# homeboard3.net
KiCad netlist of a schematic drawn in EAGLE
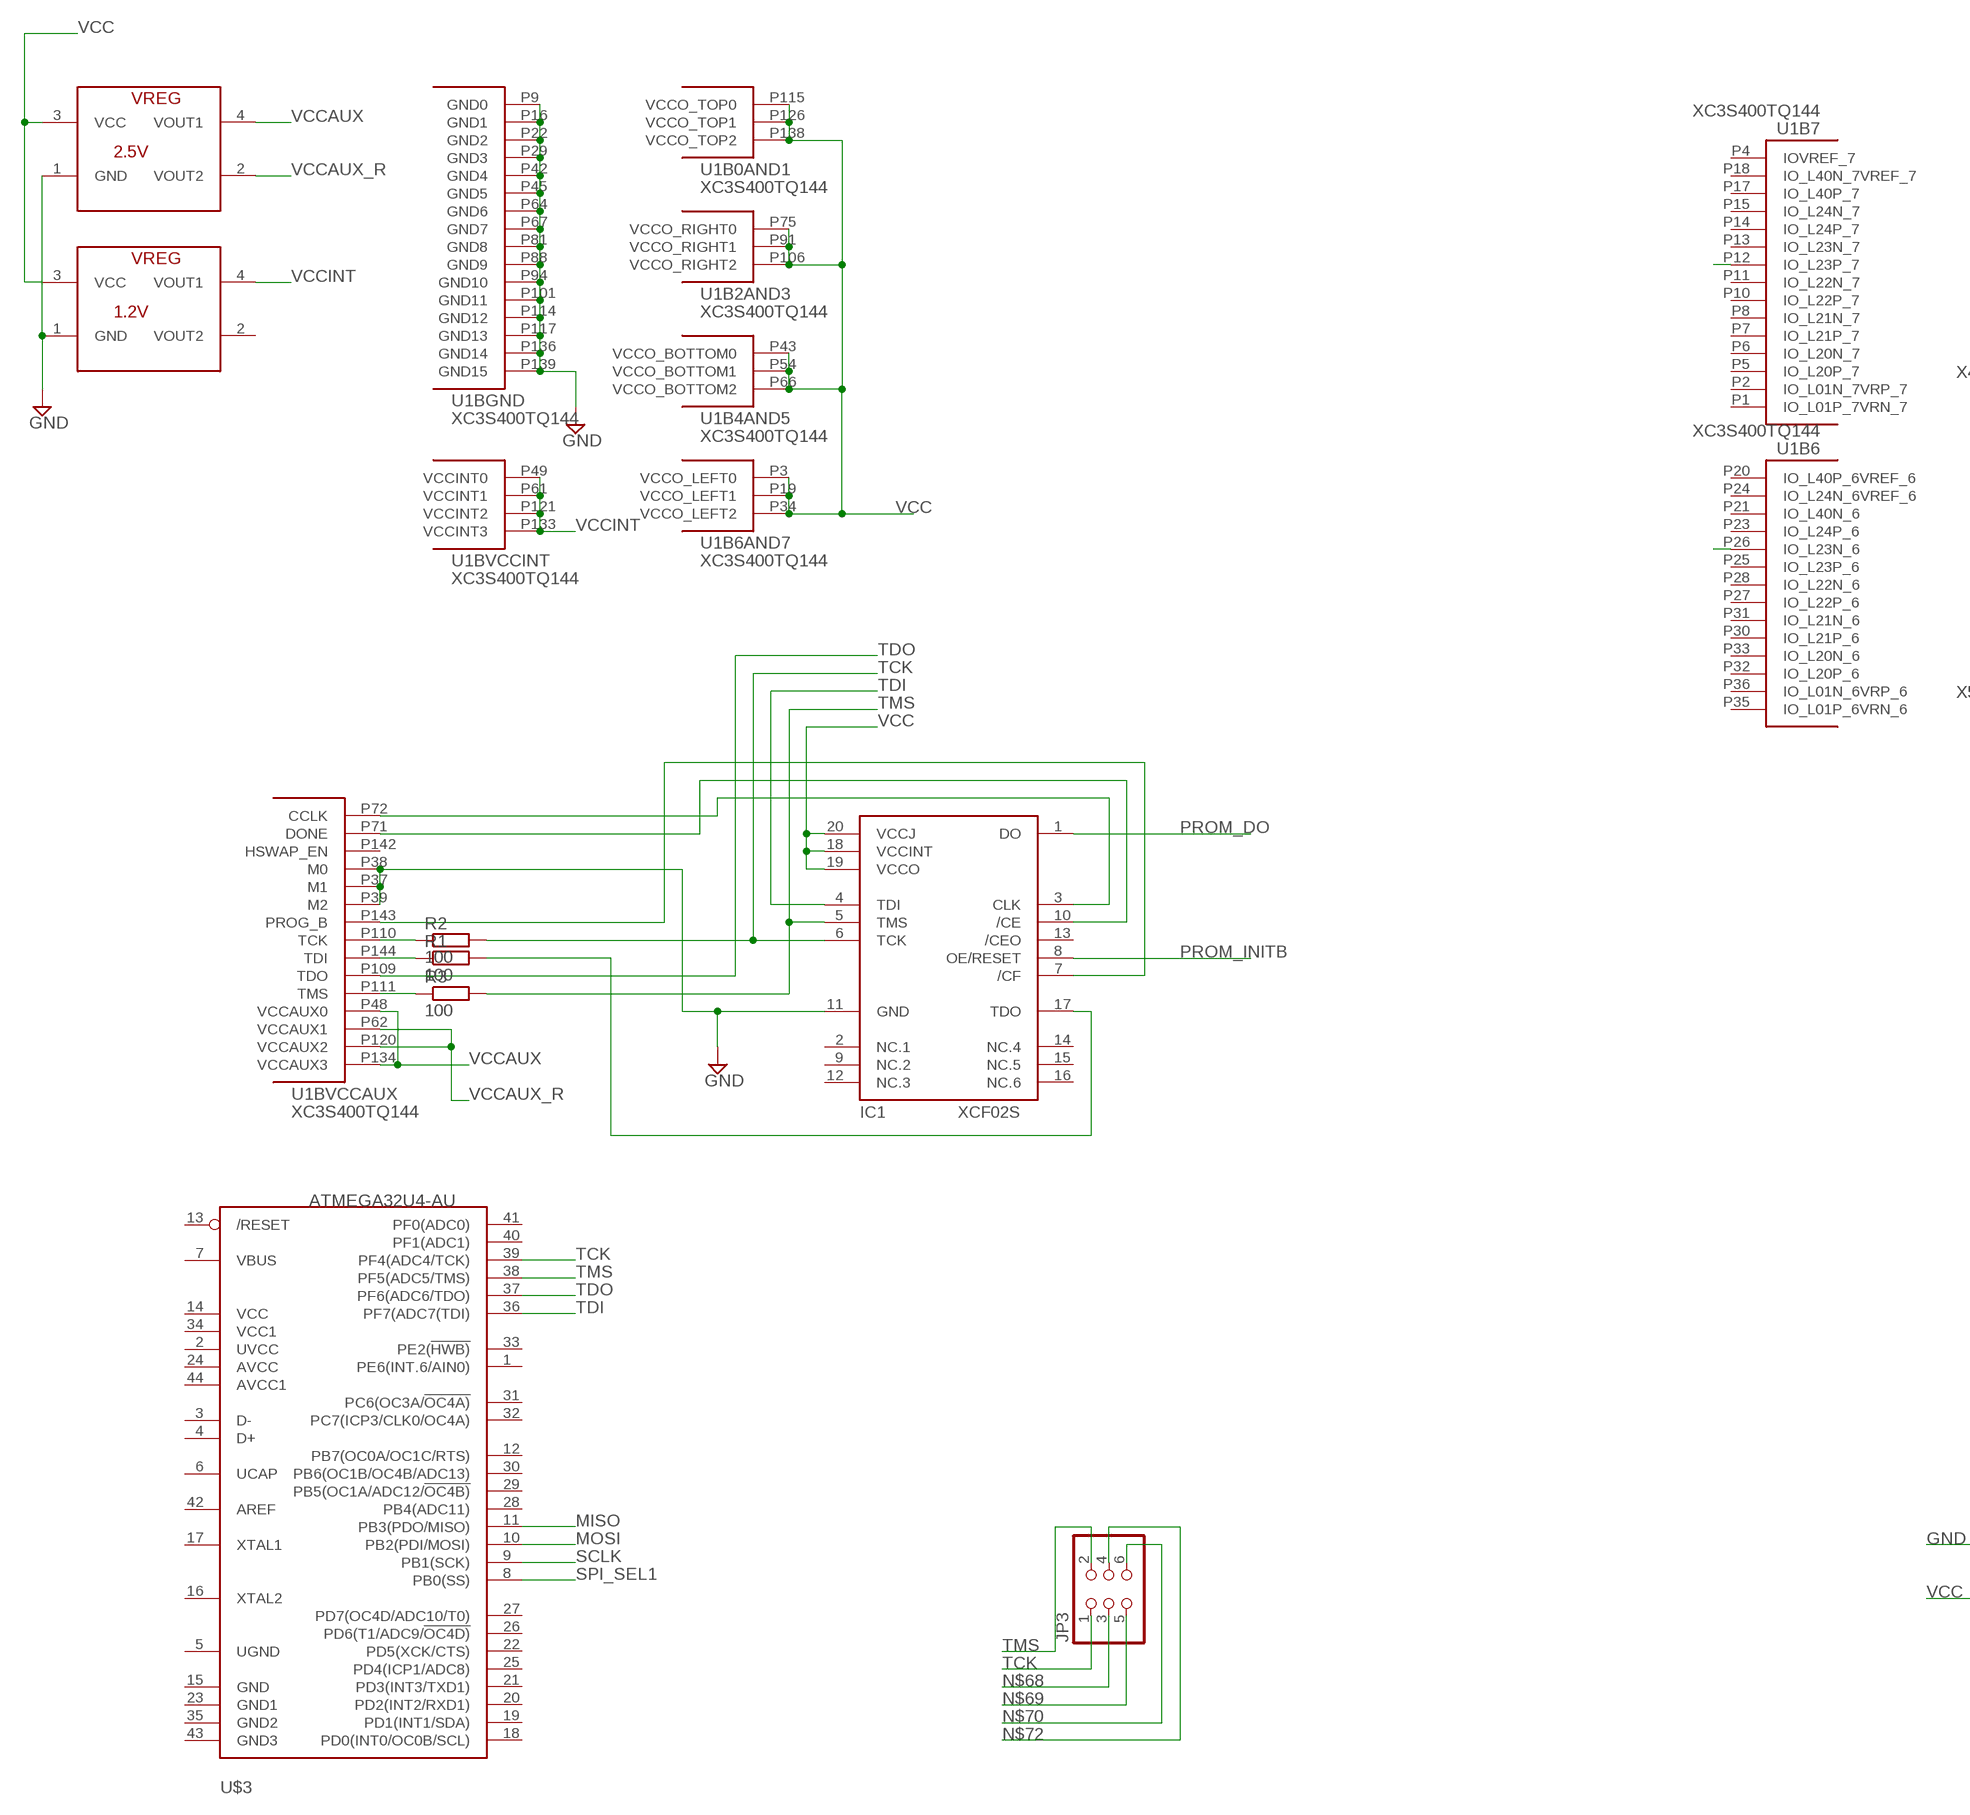
[diagram p0: schematic, sheet 1, part 1 of 3]
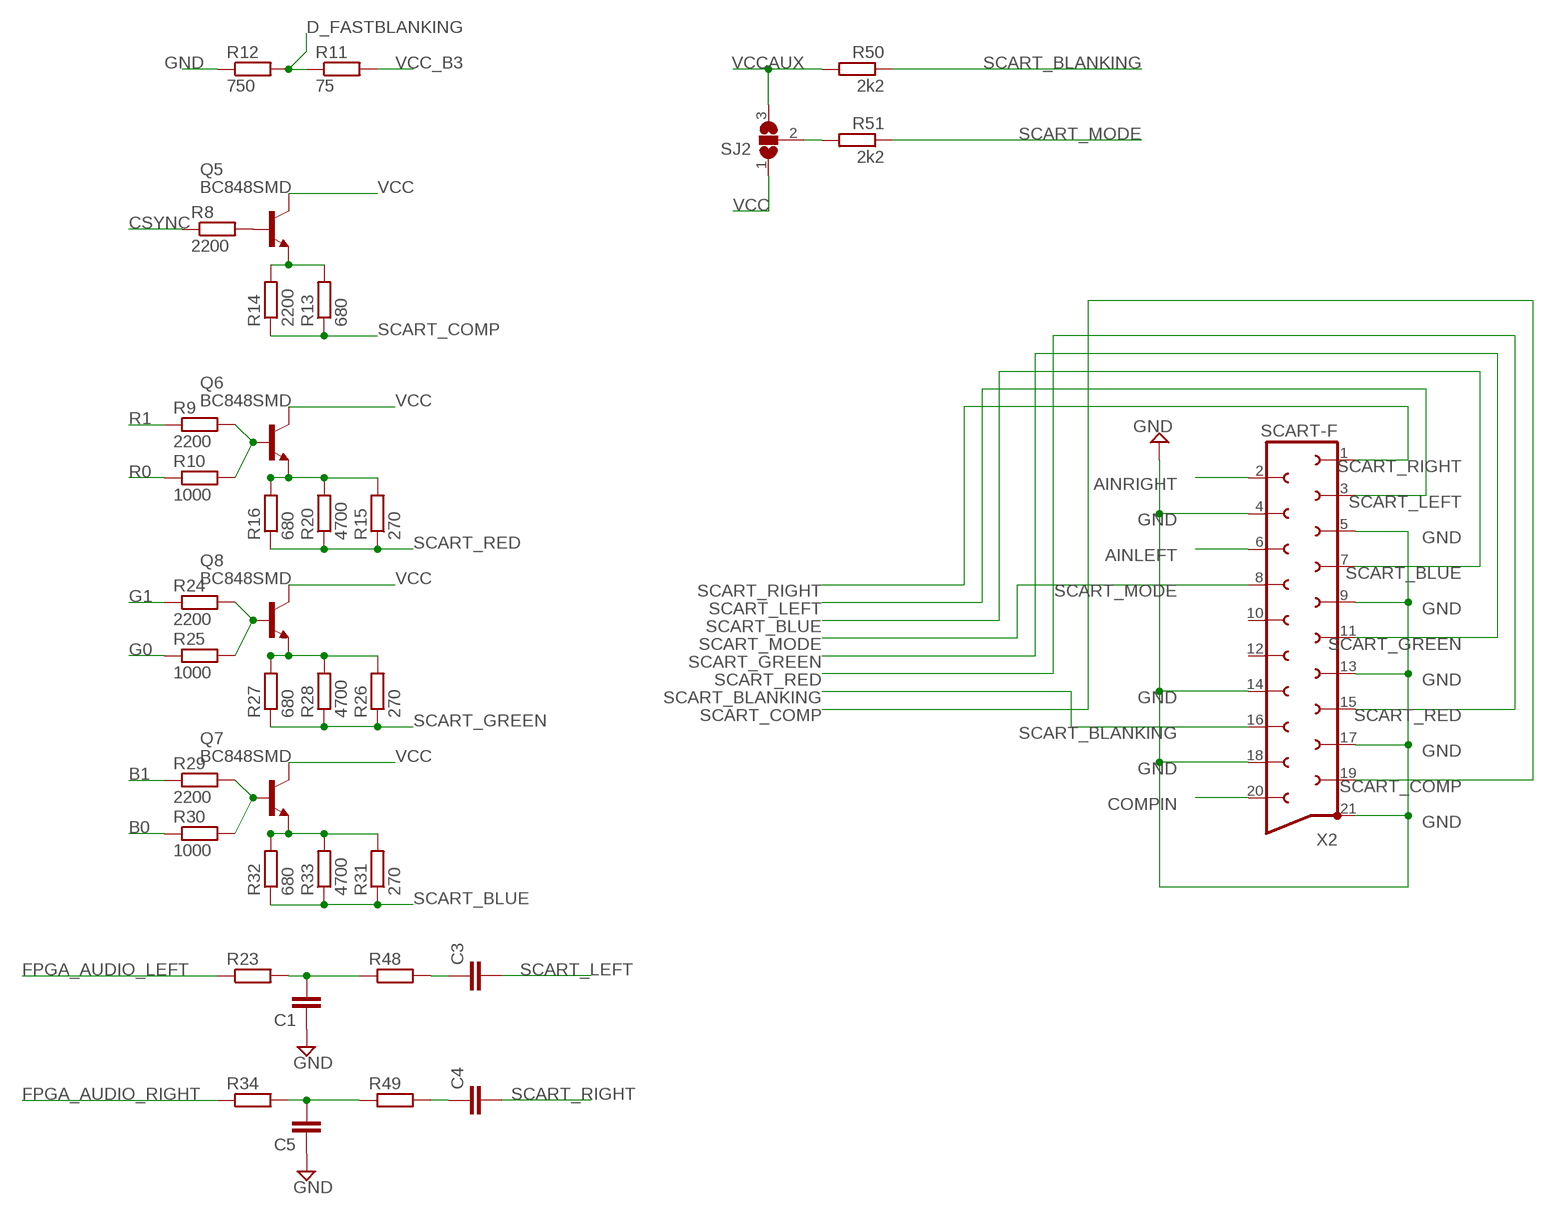
[diagram p1: schematic, sheet 1, part 2 of 3]
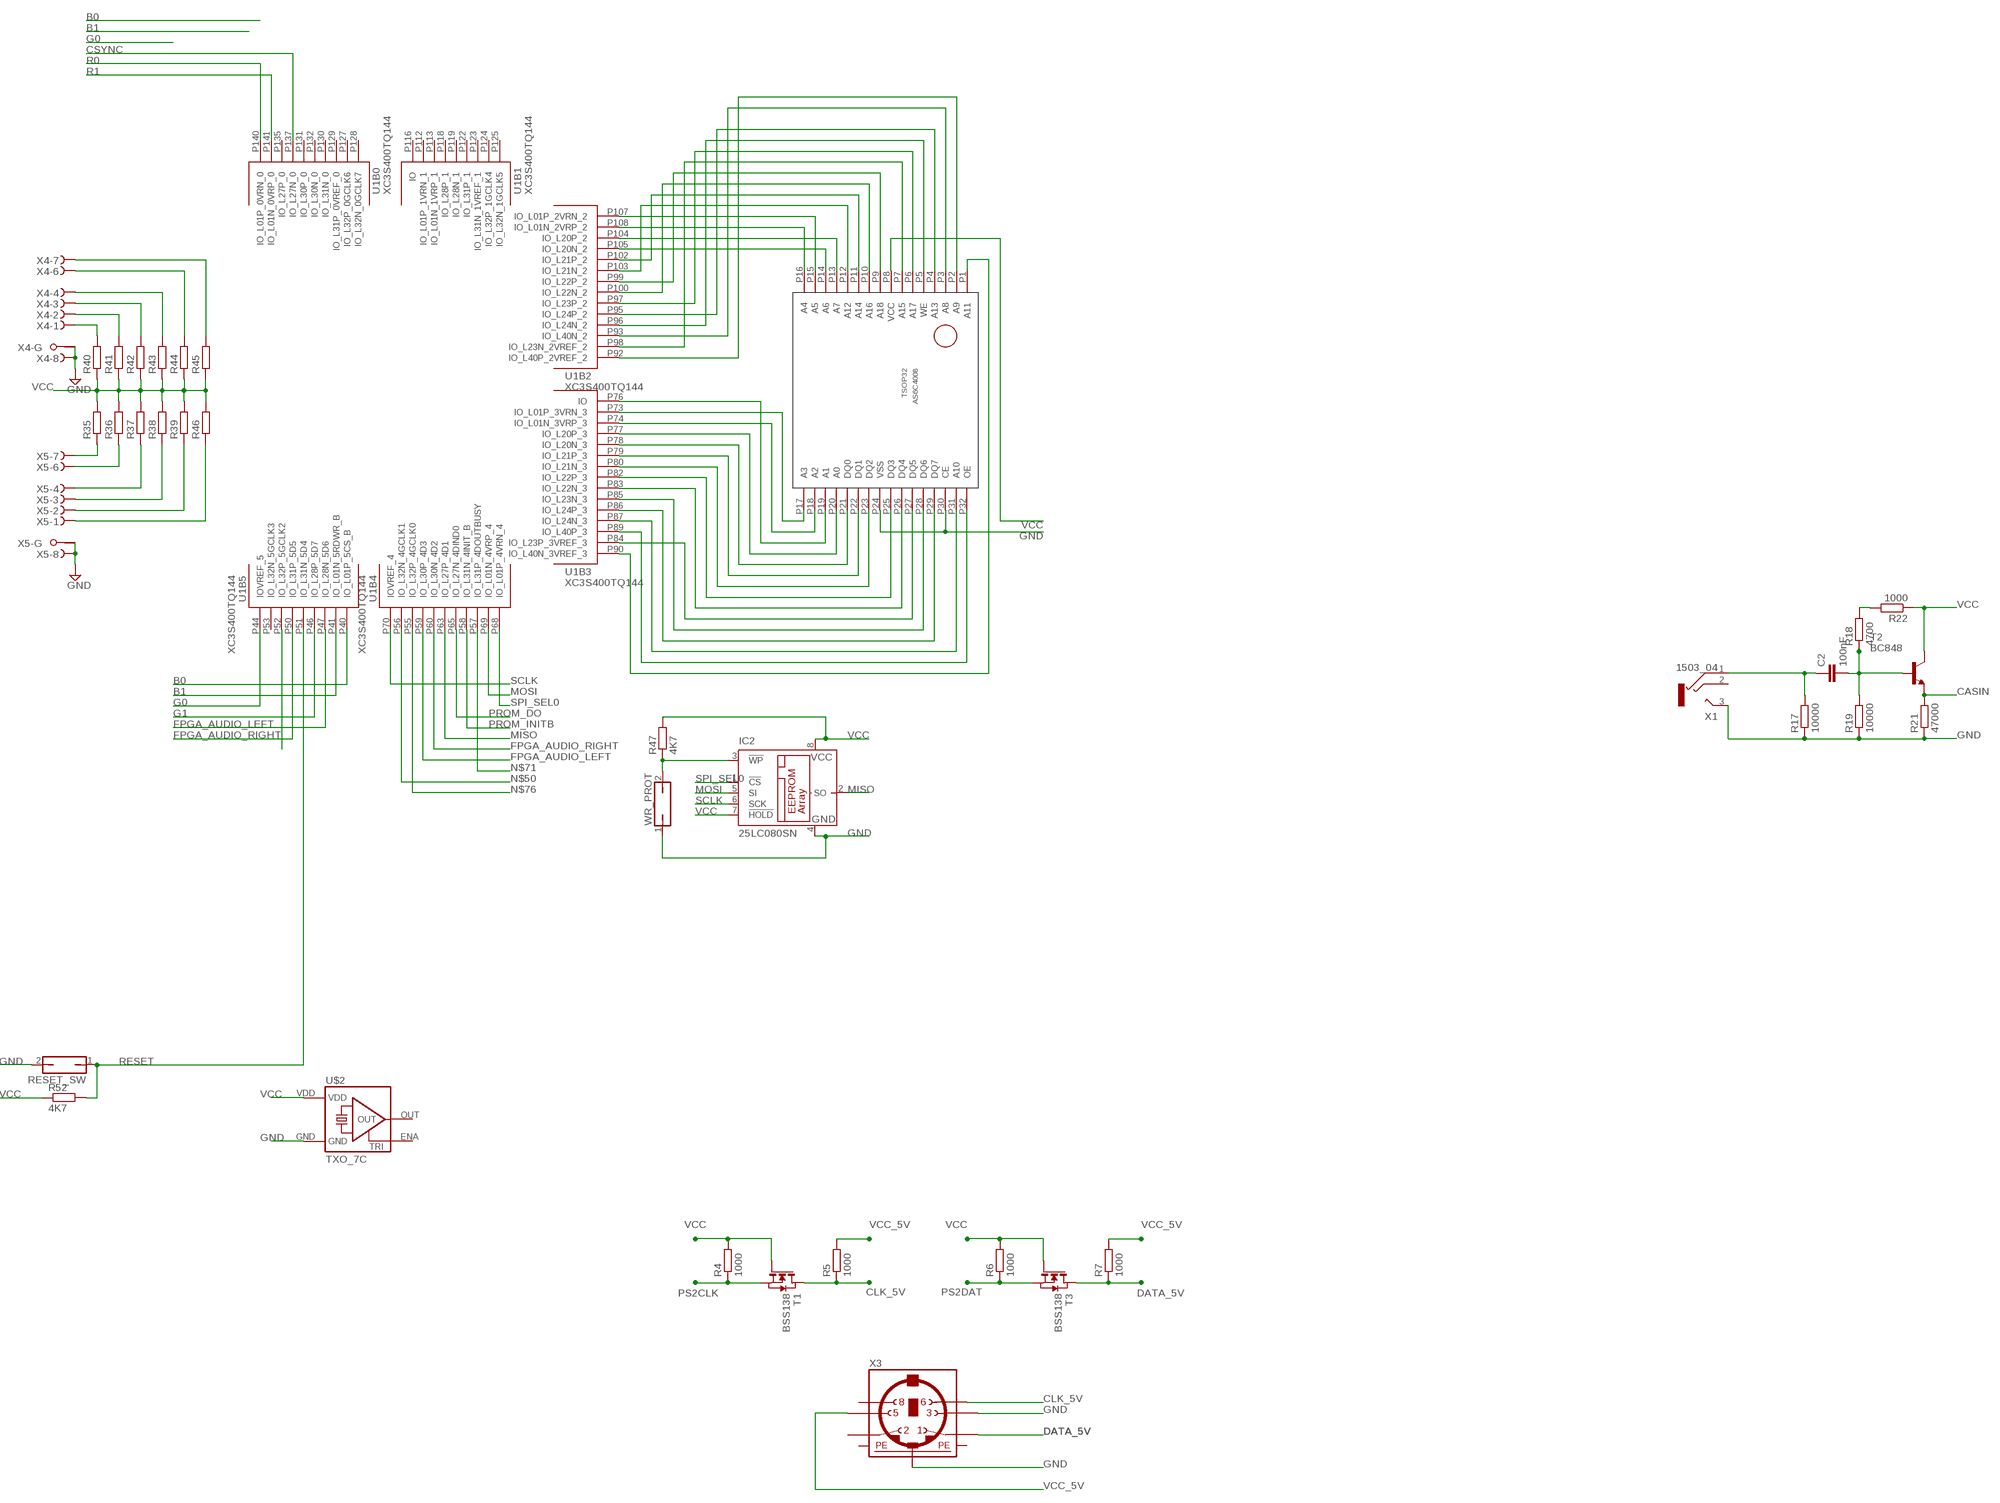
[diagram p2: schematic, sheet 1, part 3 of 3]

(export (version "E")
  (design (tool "Eeschema 10.0.6"))
  (components
    (comp (ref "C1")
      (value "C-EUC0603")
      (footprint "eagle-import:C0603")
      (libsource (lib "eagle-import") (part "C-EUC0603"))
    )
    (comp (ref "C2")
      (value "100nF")
      (footprint "eagle-import:C0603")
      (libsource (lib "eagle-import") (part "C-EUC0603"))
    )
    (comp (ref "C3")
      (value "C-EUC0603")
      (footprint "eagle-import:C0603")
      (libsource (lib "eagle-import") (part "C-EUC0603"))
    )
    (comp (ref "C4")
      (value "C-EUC0603")
      (footprint "eagle-import:C0603")
      (libsource (lib "eagle-import") (part "C-EUC0603"))
    )
    (comp (ref "C5")
      (value "C-EUC0603")
      (footprint "eagle-import:C0603")
      (libsource (lib "eagle-import") (part "C-EUC0603"))
    )
    (comp (ref "IC1")
      (value "XCF02S")
      (footprint "eagle-import:VO20")
      (libsource (lib "eagle-import") (part "XCF02S"))
    )
    (comp (ref "IC2")
      (value "25LC080SN")
      (footprint "eagle-import:SO-08")
      (fields (field (name "MF") "MICROCHIP") (field (name "MPN") "25LC080/SN"))
      (libsource (lib "eagle-import") (part "25SNLC080"))
    )
    (comp (ref "JP3")
      (value "PINHD-2X3")
      (footprint "eagle-import:2X03")
      (libsource (lib "eagle-import") (part "PINHD-2X3"))
    )
    (comp (ref "Q5")
      (value "BC848SMD")
      (footprint "eagle-import:SOT23")
      (libsource (lib "eagle-import") (part "BC848SMD"))
    )
    (comp (ref "Q6")
      (value "BC848SMD")
      (footprint "eagle-import:SOT23")
      (libsource (lib "eagle-import") (part "BC848SMD"))
    )
    (comp (ref "Q7")
      (value "BC848SMD")
      (footprint "eagle-import:SOT23")
      (libsource (lib "eagle-import") (part "BC848SMD"))
    )
    (comp (ref "Q8")
      (value "BC848SMD")
      (footprint "eagle-import:SOT23")
      (libsource (lib "eagle-import") (part "BC848SMD"))
    )
    (comp (ref "R1")
      (value "100")
      (footprint "eagle-import:R0805")
      (libsource (lib "eagle-import") (part "R-EU_R0805"))
    )
    (comp (ref "R2")
      (value "100")
      (footprint "eagle-import:R0805")
      (libsource (lib "eagle-import") (part "R-EU_R0805"))
    )
    (comp (ref "R3")
      (value "100")
      (footprint "eagle-import:R0805")
      (libsource (lib "eagle-import") (part "R-EU_R0805"))
    )
    (comp (ref "R4")
      (value "1000")
      (footprint "eagle-import:R0805")
      (libsource (lib "eagle-import") (part "R-EU_R0805"))
    )
    (comp (ref "R5")
      (value "1000")
      (footprint "eagle-import:R0805")
      (libsource (lib "eagle-import") (part "R-EU_R0805"))
    )
    (comp (ref "R6")
      (value "1000")
      (footprint "eagle-import:R0805")
      (libsource (lib "eagle-import") (part "R-EU_R0805"))
    )
    (comp (ref "R7")
      (value "1000")
      (footprint "eagle-import:R0805")
      (libsource (lib "eagle-import") (part "R-EU_R0805"))
    )
    (comp (ref "R8")
      (value "2200")
      (footprint "eagle-import:R0805")
      (libsource (lib "eagle-import") (part "R-EU_R0805"))
    )
    (comp (ref "R9")
      (value "2200")
      (footprint "eagle-import:R0805")
      (libsource (lib "eagle-import") (part "R-EU_R0805"))
    )
    (comp (ref "R10")
      (value "1000")
      (footprint "eagle-import:R0805")
      (libsource (lib "eagle-import") (part "R-EU_R0805"))
    )
    (comp (ref "R11")
      (value "75")
      (footprint "eagle-import:R0805")
      (libsource (lib "eagle-import") (part "R-EU_R0805"))
    )
    (comp (ref "R12")
      (value "750")
      (footprint "eagle-import:R0805")
      (libsource (lib "eagle-import") (part "R-EU_R0805"))
    )
    (comp (ref "R13")
      (value "680")
      (footprint "eagle-import:R0805")
      (libsource (lib "eagle-import") (part "R-EU_R0805"))
    )
    (comp (ref "R14")
      (value "2200")
      (footprint "eagle-import:R0805")
      (libsource (lib "eagle-import") (part "R-EU_R0805"))
    )
    (comp (ref "R15")
      (value "270")
      (footprint "eagle-import:R0805")
      (libsource (lib "eagle-import") (part "R-EU_R0805"))
    )
    (comp (ref "R16")
      (value "680")
      (footprint "eagle-import:R0805")
      (libsource (lib "eagle-import") (part "R-EU_R0805"))
    )
    (comp (ref "R17")
      (value "10000")
      (footprint "eagle-import:R0805")
      (libsource (lib "eagle-import") (part "R-EU_R0805"))
    )
    (comp (ref "R18")
      (value "4700")
      (footprint "eagle-import:R0805")
      (libsource (lib "eagle-import") (part "R-EU_R0805"))
    )
    (comp (ref "R19")
      (value "10000")
      (footprint "eagle-import:R0805")
      (libsource (lib "eagle-import") (part "R-EU_R0805"))
    )
    (comp (ref "R20")
      (value "4700")
      (footprint "eagle-import:R0805")
      (libsource (lib "eagle-import") (part "R-EU_R0805"))
    )
    (comp (ref "R21")
      (value "47000")
      (footprint "eagle-import:R0805")
      (libsource (lib "eagle-import") (part "R-EU_R0805"))
    )
    (comp (ref "R22")
      (value "1000")
      (footprint "eagle-import:R0805")
      (libsource (lib "eagle-import") (part "R-EU_R0805"))
    )
    (comp (ref "R23")
      (value "R-EU_M0805")
      (footprint "eagle-import:M0805")
      (libsource (lib "eagle-import") (part "resistor_R-EU_M0805"))
    )
    (comp (ref "R24")
      (value "2200")
      (footprint "eagle-import:R0805")
      (libsource (lib "eagle-import") (part "R-EU_R0805"))
    )
    (comp (ref "R25")
      (value "1000")
      (footprint "eagle-import:R0805")
      (libsource (lib "eagle-import") (part "R-EU_R0805"))
    )
    (comp (ref "R26")
      (value "270")
      (footprint "eagle-import:R0805")
      (libsource (lib "eagle-import") (part "R-EU_R0805"))
    )
    (comp (ref "R27")
      (value "680")
      (footprint "eagle-import:R0805")
      (libsource (lib "eagle-import") (part "R-EU_R0805"))
    )
    (comp (ref "R28")
      (value "4700")
      (footprint "eagle-import:R0805")
      (libsource (lib "eagle-import") (part "R-EU_R0805"))
    )
    (comp (ref "R29")
      (value "2200")
      (footprint "eagle-import:R0805")
      (libsource (lib "eagle-import") (part "R-EU_R0805"))
    )
    (comp (ref "R30")
      (value "1000")
      (footprint "eagle-import:R0805")
      (libsource (lib "eagle-import") (part "R-EU_R0805"))
    )
    (comp (ref "R31")
      (value "270")
      (footprint "eagle-import:R0805")
      (libsource (lib "eagle-import") (part "R-EU_R0805"))
    )
    (comp (ref "R32")
      (value "680")
      (footprint "eagle-import:R0805")
      (libsource (lib "eagle-import") (part "R-EU_R0805"))
    )
    (comp (ref "R33")
      (value "4700")
      (footprint "eagle-import:R0805")
      (libsource (lib "eagle-import") (part "R-EU_R0805"))
    )
    (comp (ref "R34")
      (value "R-EU_M0805")
      (footprint "eagle-import:M0805")
      (libsource (lib "eagle-import") (part "resistor_R-EU_M0805"))
    )
    (comp (ref "R35")
      (value "R-EU_M0805")
      (footprint "eagle-import:M0805")
      (libsource (lib "eagle-import") (part "resistor_R-EU_M0805"))
    )
    (comp (ref "R36")
      (value "R-EU_M0805")
      (footprint "eagle-import:M0805")
      (libsource (lib "eagle-import") (part "resistor_R-EU_M0805"))
    )
    (comp (ref "R37")
      (value "R-EU_M0805")
      (footprint "eagle-import:M0805")
      (libsource (lib "eagle-import") (part "resistor_R-EU_M0805"))
    )
    (comp (ref "R38")
      (value "R-EU_M0805")
      (footprint "eagle-import:M0805")
      (libsource (lib "eagle-import") (part "resistor_R-EU_M0805"))
    )
    (comp (ref "R39")
      (value "R-EU_M0805")
      (footprint "eagle-import:M0805")
      (libsource (lib "eagle-import") (part "resistor_R-EU_M0805"))
    )
    (comp (ref "R40")
      (value "R-EU_M0805")
      (footprint "eagle-import:M0805")
      (libsource (lib "eagle-import") (part "resistor_R-EU_M0805"))
    )
    (comp (ref "R41")
      (value "R-EU_M0805")
      (footprint "eagle-import:M0805")
      (libsource (lib "eagle-import") (part "resistor_R-EU_M0805"))
    )
    (comp (ref "R42")
      (value "R-EU_M0805")
      (footprint "eagle-import:M0805")
      (libsource (lib "eagle-import") (part "resistor_R-EU_M0805"))
    )
    (comp (ref "R43")
      (value "R-EU_M0805")
      (footprint "eagle-import:M0805")
      (libsource (lib "eagle-import") (part "resistor_R-EU_M0805"))
    )
    (comp (ref "R44")
      (value "R-EU_M0805")
      (footprint "eagle-import:M0805")
      (libsource (lib "eagle-import") (part "resistor_R-EU_M0805"))
    )
    (comp (ref "R45")
      (value "R-EU_M0805")
      (footprint "eagle-import:M0805")
      (libsource (lib "eagle-import") (part "resistor_R-EU_M0805"))
    )
    (comp (ref "R46")
      (value "R-EU_M0805")
      (footprint "eagle-import:M0805")
      (libsource (lib "eagle-import") (part "resistor_R-EU_M0805"))
    )
    (comp (ref "R47")
      (value "4K7")
      (footprint "eagle-import:R0805")
      (libsource (lib "eagle-import") (part "R-EU_R0805"))
    )
    (comp (ref "R48")
      (value "R-EU_M0805")
      (footprint "eagle-import:M0805")
      (libsource (lib "eagle-import") (part "resistor_R-EU_M0805"))
    )
    (comp (ref "R49")
      (value "R-EU_M0805")
      (footprint "eagle-import:M0805")
      (libsource (lib "eagle-import") (part "resistor_R-EU_M0805"))
    )
    (comp (ref "R50")
      (value "2k2")
      (footprint "eagle-import:M0805")
      (libsource (lib "eagle-import") (part "resistor_R-EU_M0805"))
    )
    (comp (ref "R51")
      (value "2k2")
      (footprint "eagle-import:M0805")
      (libsource (lib "eagle-import") (part "resistor_R-EU_M0805"))
    )
    (comp (ref "R52")
      (value "4K7")
      (footprint "eagle-import:M0805")
      (libsource (lib "eagle-import") (part "resistor_R-EU_M0805"))
    )
    (comp (ref "REG1.2")
      (value "1.2V")
      (footprint "eagle-import:SOT223")
      (libsource (lib "eagle-import") (part "NX1117"))
    )
    (comp (ref "REG2.5")
      (value "2.5V")
      (footprint "eagle-import:SOT223")
      (libsource (lib "eagle-import") (part "NX1117"))
    )
    (comp (ref "RESET_SW")
      (value "JP1Q")
      (footprint "eagle-import:JP1")
      (libsource (lib "eagle-import") (part "JP1Q"))
    )
    (comp (ref "SJ2")
      (value "SJ2W")
      (footprint "eagle-import:SJ_2")
      (libsource (lib "eagle-import") (part "SJ2W"))
    )
    (comp (ref "T1")
      (value "BSS138")
      (footprint "eagle-import:SOT-23")
      (libsource (lib "eagle-import") (part "NMOSSOT23"))
    )
    (comp (ref "T2")
      (value "BC848")
      (footprint "eagle-import:SOT23")
      (libsource (lib "eagle-import") (part "BC848"))
    )
    (comp (ref "T3")
      (value "BSS138")
      (footprint "eagle-import:SOT-23")
      (libsource (lib "eagle-import") (part "NMOSSOT23"))
    )
    (comp (ref "U$1")
      (value "AS6C4008")
      (footprint "eagle-import:TSOP32")
      (libsource (lib "eagle-import") (part "AS6C4008"))
    )
    (comp (ref "U$2")
      (value "TXO_7C")
      (footprint "eagle-import:OSC_7C")
      (libsource (lib "eagle-import") (part "TXO_7C"))
    )
    (comp (ref "U$3")
      (value "ATMEGA32U4-AU")
      (footprint "eagle-import:TQFP44")
      (libsource (lib "eagle-import") (part "ATMEGA32U4-AU"))
    )
    (comp (ref "U1")
      (value "XC3S400TQ144")
      (footprint "eagle-import:TQ144")
      (libsource (lib "eagle-import") (part "XC3S400TQ144"))
    )
    (comp (ref "WR_PROT")
      (value "JP1Q")
      (footprint "eagle-import:JP1")
      (libsource (lib "eagle-import") (part "JP1Q"))
    )
    (comp (ref "X1")
      (value "1503_04")
      (footprint "eagle-import:1503_04")
      (libsource (lib "eagle-import") (part "1503_04"))
    )
    (comp (ref "X2")
      (value "SCART-F")
      (footprint "eagle-import:SCART-F")
      (libsource (lib "eagle-import") (part "SCART-F"))
    )
    (comp (ref "X3")
      (value "MINI_DIN_6")
      (footprint "eagle-import:M_DIN6")
      (libsource (lib "eagle-import") (part "MINI_DIN_6"))
    )
    (comp (ref "X4")
      (value "F09HPS")
      (footprint "eagle-import:F09HP")
      (libsource (lib "eagle-import") (part "F09HPS"))
    )
    (comp (ref "X5")
      (value "F09HPS")
      (footprint "eagle-import:F09HP")
      (libsource (lib "eagle-import") (part "F09HPS"))
    )
  )
  (nets
    (net (code "1") (name "/AINLEFT") (class "Default")
      (node (ref "X2") (pin "6") (pinfunction "6_6") (pintype "passive"))
    )
    (net (code "2") (name "/AINRIGHT") (class "Default")
      (node (ref "X2") (pin "2") (pinfunction "2_2") (pintype "passive"))
    )
    (net (code "3") (name "/B0") (class "Default")
      (node (ref "R30") (pin "1") (pinfunction "1_1") (pintype "passive"))
      (node (ref "U1") (pin "P40") (pinfunction "IO_L01P_5CS_B_P40") (pintype "bidirectional"))
    )
    (net (code "4") (name "/B1") (class "Default")
      (node (ref "R29") (pin "1") (pinfunction "1_1") (pintype "passive"))
      (node (ref "U1") (pin "P41") (pinfunction "IO_L01N_5RDWR_B_P41") (pintype "bidirectional"))
    )
    (net (code "5") (name "/CASIN") (class "Default")
      (node (ref "R21") (pin "2") (pinfunction "2_2") (pintype "passive"))
      (node (ref "T2") (pin "2") (pinfunction "E_2") (pintype "passive"))
    )
    (net (code "6") (name "/CLK_5V") (class "Default")
      (node (ref "R5") (pin "1") (pinfunction "1_1") (pintype "passive"))
      (node (ref "T1") (pin "1") (pinfunction "D_1") (pintype "passive"))
      (node (ref "X3") (pin "6") (pinfunction "6_6") (pintype "passive"))
    )
    (net (code "7") (name "/COMPIN") (class "Default")
      (node (ref "X2") (pin "20") (pinfunction "20_20") (pintype "passive"))
    )
    (net (code "8") (name "/CSYNC") (class "Default")
      (node (ref "R8") (pin "1") (pinfunction "1_1") (pintype "passive"))
      (node (ref "U1") (pin "P137") (pinfunction "IO_L27N_0_P137") (pintype "bidirectional"))
    )
    (net (code "9") (name "/DATA_5V") (class "Default")
      (node (ref "R7") (pin "1") (pinfunction "1_1") (pintype "passive"))
      (node (ref "T3") (pin "1") (pinfunction "D_1") (pintype "passive"))
      (node (ref "X3") (pin "1") (pinfunction "1_1") (pintype "passive"))
    )
    (net (code "10") (name "/D_FASTBLANKING") (class "Default")
      (node (ref "R11") (pin "1") (pinfunction "1_1") (pintype "passive"))
      (node (ref "R12") (pin "2") (pinfunction "2_2") (pintype "passive"))
    )
    (net (code "11") (name "/FPGA_AUDIO_LEFT") (class "Default")
      (node (ref "R23") (pin "1") (pinfunction "1_1") (pintype "passive"))
      (node (ref "U1") (pin "P47") (pinfunction "IO_L28N_5D6_P47") (pintype "bidirectional"))
      (node (ref "U1") (pin "P59") (pinfunction "IO_L30P_4D3_P59") (pintype "bidirectional"))
    )
    (net (code "12") (name "/FPGA_AUDIO_RIGHT") (class "Default")
      (node (ref "R34") (pin "1") (pinfunction "1_1") (pintype "passive"))
      (node (ref "U1") (pin "P50") (pinfunction "IO_L31P_5D5_P50") (pintype "bidirectional"))
      (node (ref "U1") (pin "P60") (pinfunction "IO_L30N_4D2_P60") (pintype "bidirectional"))
    )
    (net (code "13") (name "/G0") (class "Default")
      (node (ref "R25") (pin "1") (pinfunction "1_1") (pintype "passive"))
      (node (ref "U1") (pin "P44") (pinfunction "IOVREF_5_P44") (pintype "bidirectional"))
    )
    (net (code "14") (name "/G1") (class "Default")
      (node (ref "R24") (pin "1") (pinfunction "1_1") (pintype "passive"))
      (node (ref "U1") (pin "P46") (pinfunction "IO_L28P_5D7_P46") (pintype "bidirectional"))
    )
    (net (code "15") (name "/MISO") (class "Default")
      (node (ref "IC2") (pin "2") (pinfunction "SO_2") (pintype "bidirectional"))
      (node (ref "U$3") (pin "11") (pinfunction "PB3(PDO/MISO)_11") (pintype "bidirectional"))
      (node (ref "U1") (pin "P63") (pinfunction "IO_L27P_4D1_P63") (pintype "bidirectional"))
    )
    (net (code "16") (name "/MOSI") (class "Default")
      (node (ref "IC2") (pin "5") (pinfunction "SI_5") (pintype "input"))
      (node (ref "U$3") (pin "10") (pinfunction "PB2(PDI/MOSI)_10") (pintype "bidirectional"))
      (node (ref "U1") (pin "P69") (pinfunction "IO_L01N_4VRP_4_P69") (pintype "bidirectional"))
    )
    (net (code "17") (name "/N$50") (class "Default")
      (node (ref "U1") (pin "P56") (pinfunction "IO_L32N_4GCLK1_P56") (pintype "bidirectional"))
    )
    (net (code "18") (name "/N$68") (class "Default")
      (node (ref "JP3") (pin "3") (pinfunction "3_3") (pintype "passive"))
    )
    (net (code "19") (name "/N$69") (class "Default")
      (node (ref "JP3") (pin "5") (pinfunction "5_5") (pintype "passive"))
    )
    (net (code "20") (name "/N$70") (class "Default")
      (node (ref "JP3") (pin "6") (pinfunction "6_6") (pintype "passive"))
    )
    (net (code "21") (name "/N$71") (class "Default")
      (node (ref "U1") (pin "P57") (pinfunction "IO_L31P_4DOUTBUSY_P57") (pintype "bidirectional"))
    )
    (net (code "22") (name "/N$72") (class "Default")
      (node (ref "JP3") (pin "4") (pinfunction "4_4") (pintype "passive"))
    )
    (net (code "23") (name "/N$76") (class "Default")
      (node (ref "U1") (pin "P55") (pinfunction "IO_L32P_4GCLK0_P55") (pintype "bidirectional"))
    )
    (net (code "24") (name "/PE1") (class "Default")
      (node (ref "X3") (pin "SH1") (pinfunction "PE1_SH1") (pintype "power_in"))
    )
    (net (code "25") (name "/PE3") (class "Default")
      (node (ref "X3") (pin "SH3") (pinfunction "PE3_SH3") (pintype "power_in"))
    )
    (net (code "26") (name "/PROM_DO") (class "Default")
      (node (ref "IC1") (pin "1") (pinfunction "DO_1") (pintype "bidirectional"))
      (node (ref "U1") (pin "P65") (pinfunction "IO_L27N_4DIND0_P65") (pintype "bidirectional"))
    )
    (net (code "27") (name "/PROM_INITB") (class "Default")
      (node (ref "IC1") (pin "8") (pinfunction "OE/RESET_8") (pintype "bidirectional"))
      (node (ref "U1") (pin "P58") (pinfunction "IO_L31N_4INIT_B_P58") (pintype "bidirectional"))
    )
    (net (code "28") (name "/PS2CLK") (class "Default")
      (node (ref "R4") (pin "1") (pinfunction "1_1") (pintype "passive"))
      (node (ref "T1") (pin "2") (pinfunction "S_2") (pintype "passive"))
    )
    (net (code "29") (name "/PS2DAT") (class "Default")
      (node (ref "R6") (pin "1") (pinfunction "1_1") (pintype "passive"))
      (node (ref "T3") (pin "2") (pinfunction "S_2") (pintype "passive"))
    )
    (net (code "30") (name "/R0") (class "Default")
      (node (ref "R10") (pin "1") (pinfunction "1_1") (pintype "passive"))
      (node (ref "U1") (pin "P140") (pinfunction "IO_L01P_0VRN_0_P140") (pintype "bidirectional"))
    )
    (net (code "31") (name "/R1") (class "Default")
      (node (ref "R9") (pin "1") (pinfunction "1_1") (pintype "passive"))
      (node (ref "U1") (pin "P141") (pinfunction "IO_L01N_0VRP_0_P141") (pintype "bidirectional"))
    )
    (net (code "32") (name "/RESET") (class "Default")
      (node (ref "R52") (pin "2") (pinfunction "2_2") (pintype "passive"))
      (node (ref "RESET_SW") (pin "1") (pinfunction "1_1") (pintype "passive"))
      (node (ref "U1") (pin "P51") (pinfunction "IO_L31N_5D4_P51") (pintype "bidirectional"))
    )
    (net (code "33") (name "/SCART_BLANKING") (class "Default")
      (node (ref "R50") (pin "1") (pinfunction "1_1") (pintype "passive"))
      (node (ref "X2") (pin "16") (pinfunction "16_16") (pintype "passive"))
    )
    (net (code "34") (name "/SCART_BLUE") (class "Default")
      (node (ref "R31") (pin "1") (pinfunction "1_1") (pintype "passive"))
      (node (ref "R32") (pin "1") (pinfunction "1_1") (pintype "passive"))
      (node (ref "R33") (pin "1") (pinfunction "1_1") (pintype "passive"))
      (node (ref "X2") (pin "7") (pinfunction "7_7") (pintype "passive"))
    )
    (net (code "35") (name "/SCART_COMP") (class "Default")
      (node (ref "R13") (pin "1") (pinfunction "1_1") (pintype "passive"))
      (node (ref "R14") (pin "1") (pinfunction "1_1") (pintype "passive"))
      (node (ref "X2") (pin "19") (pinfunction "19_19") (pintype "passive"))
    )
    (net (code "36") (name "/SCART_GREEN") (class "Default")
      (node (ref "R26") (pin "1") (pinfunction "1_1") (pintype "passive"))
      (node (ref "R27") (pin "1") (pinfunction "1_1") (pintype "passive"))
      (node (ref "R28") (pin "1") (pinfunction "1_1") (pintype "passive"))
      (node (ref "X2") (pin "11") (pinfunction "11_11") (pintype "passive"))
    )
    (net (code "37") (name "/SCART_LEFT") (class "Default")
      (node (ref "C3") (pin "2") (pinfunction "2_2") (pintype "passive"))
      (node (ref "X2") (pin "3") (pinfunction "3_3") (pintype "passive"))
    )
    (net (code "38") (name "/SCART_MODE") (class "Default")
      (node (ref "R51") (pin "1") (pinfunction "1_1") (pintype "passive"))
      (node (ref "X2") (pin "8") (pinfunction "8_8") (pintype "passive"))
    )
    (net (code "39") (name "/SCART_RED") (class "Default")
      (node (ref "R15") (pin "1") (pinfunction "1_1") (pintype "passive"))
      (node (ref "R16") (pin "1") (pinfunction "1_1") (pintype "passive"))
      (node (ref "R20") (pin "1") (pinfunction "1_1") (pintype "passive"))
      (node (ref "X2") (pin "15") (pinfunction "15_15") (pintype "passive"))
    )
    (net (code "40") (name "/SCART_RIGHT") (class "Default")
      (node (ref "C4") (pin "2") (pinfunction "2_2") (pintype "passive"))
      (node (ref "X2") (pin "1") (pinfunction "1_1") (pintype "passive"))
    )
    (net (code "41") (name "/SCLK") (class "Default")
      (node (ref "IC2") (pin "6") (pinfunction "SCK_6") (pintype "input"))
      (node (ref "U$3") (pin "9") (pinfunction "PB1(SCK)_9") (pintype "bidirectional"))
      (node (ref "U1") (pin "P70") (pinfunction "IOVREF_4_P70") (pintype "bidirectional"))
    )
    (net (code "42") (name "/SPI_SEL0") (class "Default")
      (node (ref "IC2") (pin "1") (pinfunction "~{CS}_1") (pintype "input"))
      (node (ref "U1") (pin "P68") (pinfunction "IO_L01P_4VRN_4_P68") (pintype "bidirectional"))
    )
    (net (code "43") (name "/SPI_SEL1") (class "Default")
      (node (ref "U$3") (pin "8") (pinfunction "PB0(SS)_8") (pintype "bidirectional"))
    )
    (net (code "44") (name "/TCK") (class "Default")
      (node (ref "IC1") (pin "6") (pinfunction "TCK_6") (pintype "bidirectional"))
      (node (ref "JP3") (pin "1") (pinfunction "1_1") (pintype "passive"))
      (node (ref "R2") (pin "2") (pinfunction "2_2") (pintype "passive"))
      (node (ref "U$3") (pin "39") (pinfunction "PF4(ADC4/TCK)_39") (pintype "bidirectional"))
    )
    (net (code "45") (name "/TDI") (class "Default")
      (node (ref "IC1") (pin "4") (pinfunction "TDI_4") (pintype "bidirectional"))
      (node (ref "U$3") (pin "36") (pinfunction "PF7(ADC7(TDI)_36") (pintype "bidirectional"))
    )
    (net (code "46") (name "/TDO") (class "Default")
      (node (ref "U$3") (pin "37") (pinfunction "PF6(ADC6/TDO)_37") (pintype "bidirectional"))
      (node (ref "U1") (pin "P109") (pinfunction "TDO_P109") (pintype "bidirectional"))
    )
    (net (code "47") (name "/TMS") (class "Default")
      (node (ref "IC1") (pin "5") (pinfunction "TMS_5") (pintype "bidirectional"))
      (node (ref "JP3") (pin "2") (pinfunction "2_2") (pintype "passive"))
      (node (ref "R3") (pin "2") (pinfunction "2_2") (pintype "passive"))
      (node (ref "U$3") (pin "38") (pinfunction "PF5(ADC5/TMS)_38") (pintype "bidirectional"))
    )
    (net (code "48") (name "/VCC") (class "Default")
      (node (ref "IC1") (pin "18") (pinfunction "VCCINT_18") (pintype "bidirectional"))
      (node (ref "IC1") (pin "19") (pinfunction "VCCO_19") (pintype "bidirectional"))
      (node (ref "IC1") (pin "20") (pinfunction "VCCJ_20") (pintype "bidirectional"))
      (node (ref "IC2") (pin "7") (pinfunction "~{HOLD}_7") (pintype "input"))
      (node (ref "IC2") (pin "8") (pinfunction "VCC_8") (pintype "power_in"))
      (node (ref "Q5") (pin "3") (pinfunction "C_3") (pintype "passive"))
      (node (ref "Q6") (pin "3") (pinfunction "C_3") (pintype "passive"))
      (node (ref "Q7") (pin "3") (pinfunction "C_3") (pintype "passive"))
      (node (ref "Q8") (pin "3") (pinfunction "C_3") (pintype "passive"))
      (node (ref "R22") (pin "1") (pinfunction "1_1") (pintype "passive"))
      (node (ref "R35") (pin "2") (pinfunction "2_2") (pintype "passive"))
      (node (ref "R36") (pin "2") (pinfunction "2_2") (pintype "passive"))
      (node (ref "R37") (pin "2") (pinfunction "2_2") (pintype "passive"))
      (node (ref "R38") (pin "2") (pinfunction "2_2") (pintype "passive"))
      (node (ref "R39") (pin "2") (pinfunction "2_2") (pintype "passive"))
      (node (ref "R4") (pin "2") (pinfunction "2_2") (pintype "passive"))
      (node (ref "R40") (pin "1") (pinfunction "1_1") (pintype "passive"))
      (node (ref "R41") (pin "1") (pinfunction "1_1") (pintype "passive"))
      (node (ref "R42") (pin "1") (pinfunction "1_1") (pintype "passive"))
      (node (ref "R43") (pin "1") (pinfunction "1_1") (pintype "passive"))
      (node (ref "R44") (pin "1") (pinfunction "1_1") (pintype "passive"))
      (node (ref "R45") (pin "1") (pinfunction "1_1") (pintype "passive"))
      (node (ref "R46") (pin "2") (pinfunction "2_2") (pintype "passive"))
      (node (ref "R47") (pin "2") (pinfunction "2_2") (pintype "passive"))
      (node (ref "R52") (pin "1") (pinfunction "1_1") (pintype "passive"))
      (node (ref "R6") (pin "2") (pinfunction "2_2") (pintype "passive"))
      (node (ref "REG1.2") (pin "3") (pinfunction "VCC_3") (pintype "bidirectional"))
      (node (ref "REG2.5") (pin "3") (pinfunction "VCC_3") (pintype "bidirectional"))
      (node (ref "SJ2") (pin "1") (pinfunction "1_1") (pintype "passive"))
      (node (ref "T1") (pin "3") (pinfunction "G_3") (pintype "passive"))
      (node (ref "T2") (pin "3") (pinfunction "C_3") (pintype "passive"))
      (node (ref "T3") (pin "3") (pinfunction "G_3") (pintype "passive"))
      (node (ref "U$1") (pin "P8") (pinfunction "VCC_P8") (pintype "bidirectional"))
      (node (ref "U$2") (pin "VDD") (pinfunction "VDD_VDD") (pintype "power_in"))
      (node (ref "U1") (pin "P106") (pinfunction "VCCO_RIGHT2_P106") (pintype "passive"))
      (node (ref "U1") (pin "P115") (pinfunction "VCCO_TOP0_P115") (pintype "passive"))
      (node (ref "U1") (pin "P126") (pinfunction "VCCO_TOP1_P126") (pintype "passive"))
      (node (ref "U1") (pin "P138") (pinfunction "VCCO_TOP2_P138") (pintype "passive"))
      (node (ref "U1") (pin "P19") (pinfunction "VCCO_LEFT1_P19") (pintype "passive"))
      (node (ref "U1") (pin "P3") (pinfunction "VCCO_LEFT0_P3") (pintype "passive"))
      (node (ref "U1") (pin "P34") (pinfunction "VCCO_LEFT2_P34") (pintype "passive"))
      (node (ref "U1") (pin "P43") (pinfunction "VCCO_BOTTOM0_P43") (pintype "passive"))
      (node (ref "U1") (pin "P54") (pinfunction "VCCO_BOTTOM1_P54") (pintype "passive"))
      (node (ref "U1") (pin "P66") (pinfunction "VCCO_BOTTOM2_P66") (pintype "passive"))
      (node (ref "U1") (pin "P75") (pinfunction "VCCO_RIGHT0_P75") (pintype "passive"))
      (node (ref "U1") (pin "P91") (pinfunction "VCCO_RIGHT1_P91") (pintype "passive"))
    )
    (net (code "49") (name "/VCCAUX") (class "Default")
      (node (ref "R50") (pin "2") (pinfunction "2_2") (pintype "passive"))
      (node (ref "REG2.5") (pin "4") (pinfunction "VOUT1_4") (pintype "bidirectional"))
      (node (ref "SJ2") (pin "3") (pinfunction "3_3") (pintype "passive"))
      (node (ref "U1") (pin "P134") (pinfunction "VCCAUX3_P134") (pintype "passive"))
      (node (ref "U1") (pin "P48") (pinfunction "VCCAUX0_P48") (pintype "passive"))
    )
    (net (code "50") (name "/VCCAUX_R") (class "Default")
      (node (ref "REG2.5") (pin "2") (pinfunction "VOUT2_2") (pintype "bidirectional"))
      (node (ref "U1") (pin "P120") (pinfunction "VCCAUX2_P120") (pintype "passive"))
      (node (ref "U1") (pin "P62") (pinfunction "VCCAUX1_P62") (pintype "passive"))
    )
    (net (code "51") (name "/VCCINT") (class "Default")
      (node (ref "REG1.2") (pin "4") (pinfunction "VOUT1_4") (pintype "bidirectional"))
      (node (ref "U1") (pin "P121") (pinfunction "VCCINT2_P121") (pintype "passive"))
      (node (ref "U1") (pin "P133") (pinfunction "VCCINT3_P133") (pintype "passive"))
      (node (ref "U1") (pin "P49") (pinfunction "VCCINT0_P49") (pintype "passive"))
      (node (ref "U1") (pin "P61") (pinfunction "VCCINT1_P61") (pintype "passive"))
    )
    (net (code "52") (name "/VCC_5V") (class "Default")
      (node (ref "R5") (pin "2") (pinfunction "2_2") (pintype "passive"))
      (node (ref "R7") (pin "2") (pinfunction "2_2") (pintype "passive"))
      (node (ref "X3") (pin "5") (pinfunction "5_5") (pintype "passive"))
    )
    (net (code "53") (name "/VCC_B3") (class "Default")
      (node (ref "R11") (pin "2") (pinfunction "2_2") (pintype "passive"))
    )
    (net (code "54") (name "GND") (class "Default")
      (node (ref "C1") (pin "1") (pinfunction "1_1") (pintype "passive"))
      (node (ref "C5") (pin "1") (pinfunction "1_1") (pintype "passive"))
      (node (ref "IC1") (pin "11") (pinfunction "GND_11") (pintype "bidirectional"))
      (node (ref "IC2") (pin "4") (pinfunction "GND_4") (pintype "power_in"))
      (node (ref "R12") (pin "1") (pinfunction "1_1") (pintype "passive"))
      (node (ref "R17") (pin "1") (pinfunction "1_1") (pintype "passive"))
      (node (ref "R19") (pin "1") (pinfunction "1_1") (pintype "passive"))
      (node (ref "R21") (pin "1") (pinfunction "1_1") (pintype "passive"))
      (node (ref "REG1.2") (pin "1") (pinfunction "GND_1") (pintype "bidirectional"))
      (node (ref "REG2.5") (pin "1") (pinfunction "GND_1") (pintype "bidirectional"))
      (node (ref "RESET_SW") (pin "2") (pinfunction "2_2") (pintype "passive"))
      (node (ref "U$1") (pin "P24") (pinfunction "VSS_P24") (pintype "bidirectional"))
      (node (ref "U$1") (pin "P30") (pinfunction "CE_P30") (pintype "bidirectional"))
      (node (ref "U$2") (pin "GND") (pinfunction "GND_GND") (pintype "power_in"))
      (node (ref "U1") (pin "P101") (pinfunction "GND11_P101") (pintype "passive"))
      (node (ref "U1") (pin "P114") (pinfunction "GND12_P114") (pintype "passive"))
      (node (ref "U1") (pin "P117") (pinfunction "GND13_P117") (pintype "passive"))
      (node (ref "U1") (pin "P136") (pinfunction "GND14_P136") (pintype "passive"))
      (node (ref "U1") (pin "P139") (pinfunction "GND15_P139") (pintype "passive"))
      (node (ref "U1") (pin "P16") (pinfunction "GND1_P16") (pintype "passive"))
      (node (ref "U1") (pin "P22") (pinfunction "GND2_P22") (pintype "passive"))
      (node (ref "U1") (pin "P29") (pinfunction "GND3_P29") (pintype "passive"))
      (node (ref "U1") (pin "P37") (pinfunction "M1_P37") (pintype "bidirectional"))
      (node (ref "U1") (pin "P38") (pinfunction "M0_P38") (pintype "bidirectional"))
      (node (ref "U1") (pin "P39") (pinfunction "M2_P39") (pintype "bidirectional"))
      (node (ref "U1") (pin "P42") (pinfunction "GND4_P42") (pintype "passive"))
      (node (ref "U1") (pin "P45") (pinfunction "GND5_P45") (pintype "passive"))
      (node (ref "U1") (pin "P64") (pinfunction "GND6_P64") (pintype "passive"))
      (node (ref "U1") (pin "P67") (pinfunction "GND7_P67") (pintype "passive"))
      (node (ref "U1") (pin "P81") (pinfunction "GND8_P81") (pintype "passive"))
      (node (ref "U1") (pin "P88") (pinfunction "GND9_P88") (pintype "passive"))
      (node (ref "U1") (pin "P9") (pinfunction "GND0_P9") (pintype "passive"))
      (node (ref "U1") (pin "P94") (pinfunction "GND10_P94") (pintype "passive"))
      (node (ref "WR_PROT") (pin "1") (pinfunction "1_1") (pintype "passive"))
      (node (ref "X1") (pin "3") (pinfunction "2_3") (pintype "passive"))
      (node (ref "X2") (pin "13") (pinfunction "13_13") (pintype "passive"))
      (node (ref "X2") (pin "14") (pinfunction "14_14") (pintype "passive"))
      (node (ref "X2") (pin "17") (pinfunction "17_17") (pintype "passive"))
      (node (ref "X2") (pin "18") (pinfunction "18_18") (pintype "passive"))
      (node (ref "X2") (pin "21") (pinfunction "21_21") (pintype "passive"))
      (node (ref "X2") (pin "4") (pinfunction "4_4") (pintype "passive"))
      (node (ref "X2") (pin "5") (pinfunction "5_5") (pintype "passive"))
      (node (ref "X2") (pin "9") (pinfunction "9_9") (pintype "passive"))
      (node (ref "X3") (pin "3") (pinfunction "3_3") (pintype "passive"))
      (node (ref "X3") (pin "SH2") (pinfunction "PE2_SH2") (pintype "power_in"))
      (node (ref "X4") (pin "8") (pinfunction "F_8") (pintype "passive"))
      (node (ref "X4") (pin "G1") (pinfunction "G1_G1") (pintype "passive"))
      (node (ref "X5") (pin "8") (pinfunction "F_8") (pintype "passive"))
      (node (ref "X5") (pin "G1") (pinfunction "G1_G1") (pintype "passive"))
    )
    (net (code "55") (name "Net-(C1-Pad2)") (class "Default")
      (node (ref "C1") (pin "2") (pinfunction "2_2") (pintype "passive"))
      (node (ref "R23") (pin "2") (pinfunction "2_2") (pintype "passive"))
      (node (ref "R48") (pin "1") (pinfunction "1_1") (pintype "passive"))
    )
    (net (code "56") (name "Net-(C2-Pad1)") (class "Default")
      (node (ref "C2") (pin "1") (pinfunction "1_1") (pintype "passive"))
      (node (ref "R17") (pin "2") (pinfunction "2_2") (pintype "passive"))
      (node (ref "X1") (pin "1") (pinfunction "1_1") (pintype "passive"))
    )
    (net (code "57") (name "Net-(C3-Pad1)") (class "Default")
      (node (ref "C3") (pin "1") (pinfunction "1_1") (pintype "passive"))
      (node (ref "R48") (pin "2") (pinfunction "2_2") (pintype "passive"))
    )
    (net (code "58") (name "Net-(C4-Pad1)") (class "Default")
      (node (ref "C4") (pin "1") (pinfunction "1_1") (pintype "passive"))
      (node (ref "R49") (pin "2") (pinfunction "2_2") (pintype "passive"))
    )
    (net (code "59") (name "Net-(C5-Pad2)") (class "Default")
      (node (ref "C5") (pin "2") (pinfunction "2_2") (pintype "passive"))
      (node (ref "R34") (pin "2") (pinfunction "2_2") (pintype "passive"))
      (node (ref "R49") (pin "1") (pinfunction "1_1") (pintype "passive"))
    )
    (net (code "60") (name "Net-(IC1-CLK)") (class "Default")
      (node (ref "IC1") (pin "3") (pinfunction "CLK_3") (pintype "bidirectional"))
      (node (ref "U1") (pin "P72") (pinfunction "CCLK_P72") (pintype "bidirectional"))
    )
    (net (code "61") (name "Net-(IC1-TDO)") (class "Default")
      (node (ref "IC1") (pin "17") (pinfunction "TDO_17") (pintype "bidirectional"))
      (node (ref "R1") (pin "2") (pinfunction "2_2") (pintype "passive"))
    )
    (net (code "62") (name "Net-(IC1-{slash}CE)") (class "Default")
      (node (ref "IC1") (pin "10") (pinfunction "/CE_10") (pintype "bidirectional"))
      (node (ref "U1") (pin "P71") (pinfunction "DONE_P71") (pintype "bidirectional"))
    )
    (net (code "63") (name "Net-(IC1-{slash}CF)") (class "Default")
      (node (ref "IC1") (pin "7") (pinfunction "/CF_7") (pintype "bidirectional"))
      (node (ref "U1") (pin "P143") (pinfunction "PROG_B_P143") (pintype "bidirectional"))
    )
    (net (code "64") (name "Net-(IC2-~{WP})") (class "Default")
      (node (ref "IC2") (pin "3") (pinfunction "~{WP}_3") (pintype "input"))
      (node (ref "R47") (pin "1") (pinfunction "1_1") (pintype "passive"))
      (node (ref "WR_PROT") (pin "2") (pinfunction "2_2") (pintype "passive"))
    )
    (net (code "65") (name "Net-(Q5-B)") (class "Default")
      (node (ref "Q5") (pin "1") (pinfunction "B_1") (pintype "passive"))
      (node (ref "R8") (pin "2") (pinfunction "2_2") (pintype "passive"))
    )
    (net (code "66") (name "Net-(Q5-E)") (class "Default")
      (node (ref "Q5") (pin "2") (pinfunction "E_2") (pintype "passive"))
      (node (ref "R13") (pin "2") (pinfunction "2_2") (pintype "passive"))
      (node (ref "R14") (pin "2") (pinfunction "2_2") (pintype "passive"))
    )
    (net (code "67") (name "Net-(Q6-B)") (class "Default")
      (node (ref "Q6") (pin "1") (pinfunction "B_1") (pintype "passive"))
      (node (ref "R10") (pin "2") (pinfunction "2_2") (pintype "passive"))
      (node (ref "R9") (pin "2") (pinfunction "2_2") (pintype "passive"))
    )
    (net (code "68") (name "Net-(Q6-E)") (class "Default")
      (node (ref "Q6") (pin "2") (pinfunction "E_2") (pintype "passive"))
      (node (ref "R15") (pin "2") (pinfunction "2_2") (pintype "passive"))
      (node (ref "R16") (pin "2") (pinfunction "2_2") (pintype "passive"))
      (node (ref "R20") (pin "2") (pinfunction "2_2") (pintype "passive"))
    )
    (net (code "69") (name "Net-(Q7-B)") (class "Default")
      (node (ref "Q7") (pin "1") (pinfunction "B_1") (pintype "passive"))
      (node (ref "R29") (pin "2") (pinfunction "2_2") (pintype "passive"))
      (node (ref "R30") (pin "2") (pinfunction "2_2") (pintype "passive"))
    )
    (net (code "70") (name "Net-(Q7-E)") (class "Default")
      (node (ref "Q7") (pin "2") (pinfunction "E_2") (pintype "passive"))
      (node (ref "R31") (pin "2") (pinfunction "2_2") (pintype "passive"))
      (node (ref "R32") (pin "2") (pinfunction "2_2") (pintype "passive"))
      (node (ref "R33") (pin "2") (pinfunction "2_2") (pintype "passive"))
    )
    (net (code "71") (name "Net-(Q8-B)") (class "Default")
      (node (ref "Q8") (pin "1") (pinfunction "B_1") (pintype "passive"))
      (node (ref "R24") (pin "2") (pinfunction "2_2") (pintype "passive"))
      (node (ref "R25") (pin "2") (pinfunction "2_2") (pintype "passive"))
    )
    (net (code "72") (name "Net-(Q8-E)") (class "Default")
      (node (ref "Q8") (pin "2") (pinfunction "E_2") (pintype "passive"))
      (node (ref "R26") (pin "2") (pinfunction "2_2") (pintype "passive"))
      (node (ref "R27") (pin "2") (pinfunction "2_2") (pintype "passive"))
      (node (ref "R28") (pin "2") (pinfunction "2_2") (pintype "passive"))
    )
    (net (code "73") (name "Net-(R18-Pad2)") (class "Default")
      (node (ref "R18") (pin "2") (pinfunction "2_2") (pintype "passive"))
      (node (ref "R22") (pin "2") (pinfunction "2_2") (pintype "passive"))
    )
    (net (code "74") (name "Net-(R51-Pad2)") (class "Default")
      (node (ref "R51") (pin "2") (pinfunction "2_2") (pintype "passive"))
      (node (ref "SJ2") (pin "2") (pinfunction "2_2") (pintype "passive"))
    )
    (net (code "75") (name "Net-(T2-B)") (class "Default")
      (node (ref "C2") (pin "2") (pinfunction "2_2") (pintype "passive"))
      (node (ref "R18") (pin "1") (pinfunction "1_1") (pintype "passive"))
      (node (ref "R19") (pin "2") (pinfunction "2_2") (pintype "passive"))
      (node (ref "T2") (pin "1") (pinfunction "B_1") (pintype "passive"))
    )
    (net (code "76") (name "Net-(U$1-A0)") (class "Default")
      (node (ref "U$1") (pin "P20") (pinfunction "A0_P20") (pintype "bidirectional"))
      (node (ref "U1") (pin "P77") (pinfunction "IO_L20P_3_P77") (pintype "bidirectional"))
    )
    (net (code "77") (name "Net-(U$1-A1)") (class "Default")
      (node (ref "U$1") (pin "P19") (pinfunction "A1_P19") (pintype "bidirectional"))
      (node (ref "U1") (pin "P76") (pinfunction "IO_P76") (pintype "bidirectional"))
    )
    (net (code "78") (name "Net-(U$1-A2)") (class "Default")
      (node (ref "U$1") (pin "P18") (pinfunction "A2_P18") (pintype "bidirectional"))
      (node (ref "U1") (pin "P74") (pinfunction "IO_L01N_3VRP_3_P74") (pintype "bidirectional"))
    )
    (net (code "79") (name "Net-(U$1-A3)") (class "Default")
      (node (ref "U$1") (pin "P17") (pinfunction "A3_P17") (pintype "bidirectional"))
      (node (ref "U1") (pin "P73") (pinfunction "IO_L01P_3VRN_3_P73") (pintype "bidirectional"))
    )
    (net (code "80") (name "Net-(U$1-A4)") (class "Default")
      (node (ref "U$1") (pin "P16") (pinfunction "A4_P16") (pintype "bidirectional"))
      (node (ref "U1") (pin "P108") (pinfunction "IO_L01N_2VRP_2_P108") (pintype "bidirectional"))
    )
    (net (code "81") (name "Net-(U$1-A5)") (class "Default")
      (node (ref "U$1") (pin "P15") (pinfunction "A5_P15") (pintype "bidirectional"))
      (node (ref "U1") (pin "P107") (pinfunction "IO_L01P_2VRN_2_P107") (pintype "bidirectional"))
    )
    (net (code "82") (name "Net-(U$1-A6)") (class "Default")
      (node (ref "U$1") (pin "P14") (pinfunction "A6_P14") (pintype "bidirectional"))
      (node (ref "U1") (pin "P105") (pinfunction "IO_L20N_2_P105") (pintype "bidirectional"))
    )
    (net (code "83") (name "Net-(U$1-A7)") (class "Default")
      (node (ref "U$1") (pin "P13") (pinfunction "A7_P13") (pintype "bidirectional"))
      (node (ref "U1") (pin "P104") (pinfunction "IO_L20P_2_P104") (pintype "bidirectional"))
    )
    (net (code "84") (name "Net-(U$1-A8)") (class "Default")
      (node (ref "U$1") (pin "P3") (pinfunction "A8_P3") (pintype "bidirectional"))
      (node (ref "U1") (pin "P93") (pinfunction "IO_L40N_2_P93") (pintype "bidirectional"))
    )
    (net (code "85") (name "Net-(U$1-A9)") (class "Default")
      (node (ref "U$1") (pin "P2") (pinfunction "A9_P2") (pintype "bidirectional"))
      (node (ref "U1") (pin "P92") (pinfunction "IO_L40P_2VREF_2_P92") (pintype "bidirectional"))
    )
    (net (code "86") (name "Net-(U$1-A10)") (class "Default")
      (node (ref "U$1") (pin "P31") (pinfunction "A10_P31") (pintype "bidirectional"))
      (node (ref "U1") (pin "P87") (pinfunction "IO_L24N_3_P87") (pintype "bidirectional"))
    )
    (net (code "87") (name "Net-(U$1-A11)") (class "Default")
      (node (ref "U$1") (pin "P1") (pinfunction "A11_P1") (pintype "bidirectional"))
      (node (ref "U1") (pin "P90") (pinfunction "IO_L40N_3VREF_3_P90") (pintype "bidirectional"))
    )
    (net (code "88") (name "Net-(U$1-A12)") (class "Default")
      (node (ref "U$1") (pin "P12") (pinfunction "A12_P12") (pintype "bidirectional"))
      (node (ref "U1") (pin "P103") (pinfunction "IO_L21N_2_P103") (pintype "bidirectional"))
    )
    (net (code "89") (name "Net-(U$1-A13)") (class "Default")
      (node (ref "U$1") (pin "P4") (pinfunction "A13_P4") (pintype "bidirectional"))
      (node (ref "U1") (pin "P95") (pinfunction "IO_L24P_2_P95") (pintype "bidirectional"))
    )
    (net (code "90") (name "Net-(U$1-A14)") (class "Default")
      (node (ref "U$1") (pin "P11") (pinfunction "A14_P11") (pintype "bidirectional"))
      (node (ref "U1") (pin "P102") (pinfunction "IO_L21P_2_P102") (pintype "bidirectional"))
    )
    (net (code "91") (name "Net-(U$1-A15)") (class "Default")
      (node (ref "U$1") (pin "P7") (pinfunction "A15_P7") (pintype "bidirectional"))
      (node (ref "U1") (pin "P98") (pinfunction "IO_L23N_2VREF_2_P98") (pintype "bidirectional"))
    )
    (net (code "92") (name "Net-(U$1-A16)") (class "Default")
      (node (ref "U$1") (pin "P10") (pinfunction "A16_P10") (pintype "bidirectional"))
      (node (ref "U1") (pin "P100") (pinfunction "IO_L22N_2_P100") (pintype "bidirectional"))
    )
    (net (code "93") (name "Net-(U$1-A17)") (class "Default")
      (node (ref "U$1") (pin "P6") (pinfunction "A17_P6") (pintype "bidirectional"))
      (node (ref "U1") (pin "P97") (pinfunction "IO_L23P_2_P97") (pintype "bidirectional"))
    )
    (net (code "94") (name "Net-(U$1-A18)") (class "Default")
      (node (ref "U$1") (pin "P9") (pinfunction "A18_P9") (pintype "bidirectional"))
      (node (ref "U1") (pin "P99") (pinfunction "IO_L22P_2_P99") (pintype "bidirectional"))
    )
    (net (code "95") (name "Net-(U$1-DQ0)") (class "Default")
      (node (ref "U$1") (pin "P21") (pinfunction "DQ0_P21") (pintype "bidirectional"))
      (node (ref "U1") (pin "P78") (pinfunction "IO_L20N_3_P78") (pintype "bidirectional"))
    )
    (net (code "96") (name "Net-(U$1-DQ1)") (class "Default")
      (node (ref "U$1") (pin "P22") (pinfunction "DQ1_P22") (pintype "bidirectional"))
      (node (ref "U1") (pin "P79") (pinfunction "IO_L21P_3_P79") (pintype "bidirectional"))
    )
    (net (code "97") (name "Net-(U$1-DQ2)") (class "Default")
      (node (ref "U$1") (pin "P23") (pinfunction "DQ2_P23") (pintype "bidirectional"))
      (node (ref "U1") (pin "P80") (pinfunction "IO_L21N_3_P80") (pintype "bidirectional"))
    )
    (net (code "98") (name "Net-(U$1-DQ3)") (class "Default")
      (node (ref "U$1") (pin "P25") (pinfunction "DQ3_P25") (pintype "bidirectional"))
      (node (ref "U1") (pin "P82") (pinfunction "IO_L22P_3_P82") (pintype "bidirectional"))
    )
    (net (code "99") (name "Net-(U$1-DQ4)") (class "Default")
      (node (ref "U$1") (pin "P26") (pinfunction "DQ4_P26") (pintype "bidirectional"))
      (node (ref "U1") (pin "P83") (pinfunction "IO_L22N_3_P83") (pintype "bidirectional"))
    )
    (net (code "100") (name "Net-(U$1-DQ5)") (class "Default")
      (node (ref "U$1") (pin "P27") (pinfunction "DQ5_P27") (pintype "bidirectional"))
      (node (ref "U1") (pin "P84") (pinfunction "IO_L23P_3VREF_3_P84") (pintype "bidirectional"))
    )
    (net (code "101") (name "Net-(U$1-DQ6)") (class "Default")
      (node (ref "U$1") (pin "P28") (pinfunction "DQ6_P28") (pintype "bidirectional"))
      (node (ref "U1") (pin "P85") (pinfunction "IO_L23N_3_P85") (pintype "bidirectional"))
    )
    (net (code "102") (name "Net-(U$1-DQ7)") (class "Default")
      (node (ref "U$1") (pin "P29") (pinfunction "DQ7_P29") (pintype "bidirectional"))
      (node (ref "U1") (pin "P86") (pinfunction "IO_L24P_3_P86") (pintype "bidirectional"))
    )
    (net (code "103") (name "Net-(U$1-OE)") (class "Default")
      (node (ref "U$1") (pin "P32") (pinfunction "OE_P32") (pintype "bidirectional"))
      (node (ref "U1") (pin "P89") (pinfunction "IO_L40P_3_P89") (pintype "bidirectional"))
    )
    (net (code "104") (name "Net-(U$1-WE)") (class "Default")
      (node (ref "U$1") (pin "P5") (pinfunction "WE_P5") (pintype "bidirectional"))
      (node (ref "U1") (pin "P96") (pinfunction "IO_L24N_2_P96") (pintype "bidirectional"))
    )
    (net (code "105") (name "Net-(U1N-TCK)") (class "Default")
      (node (ref "R2") (pin "1") (pinfunction "1_1") (pintype "passive"))
      (node (ref "U1") (pin "P110") (pinfunction "TCK_P110") (pintype "bidirectional"))
    )
    (net (code "106") (name "Net-(U1N-TDI)") (class "Default")
      (node (ref "R1") (pin "1") (pinfunction "1_1") (pintype "passive"))
      (node (ref "U1") (pin "P144") (pinfunction "TDI_P144") (pintype "bidirectional"))
    )
    (net (code "107") (name "Net-(U1N-TMS)") (class "Default")
      (node (ref "R3") (pin "1") (pinfunction "1_1") (pintype "passive"))
      (node (ref "U1") (pin "P111") (pinfunction "TMS_P111") (pintype "bidirectional"))
    )
    (net (code "108") (name "Net-(X4A-F)") (class "Default")
      (node (ref "R40") (pin "2") (pinfunction "2_2") (pintype "passive"))
      (node (ref "X4") (pin "1") (pinfunction "F_1") (pintype "passive"))
    )
    (net (code "109") (name "Net-(X4B-F)") (class "Default")
      (node (ref "R41") (pin "2") (pinfunction "2_2") (pintype "passive"))
      (node (ref "X4") (pin "2") (pinfunction "F_2") (pintype "passive"))
    )
    (net (code "110") (name "Net-(X4C-F)") (class "Default")
      (node (ref "R42") (pin "2") (pinfunction "2_2") (pintype "passive"))
      (node (ref "X4") (pin "3") (pinfunction "F_3") (pintype "passive"))
    )
    (net (code "111") (name "Net-(X4D-F)") (class "Default")
      (node (ref "R43") (pin "2") (pinfunction "2_2") (pintype "passive"))
      (node (ref "X4") (pin "4") (pinfunction "F_4") (pintype "passive"))
    )
    (net (code "112") (name "Net-(X4F-F)") (class "Default")
      (node (ref "R44") (pin "2") (pinfunction "2_2") (pintype "passive"))
      (node (ref "X4") (pin "6") (pinfunction "F_6") (pintype "passive"))
    )
    (net (code "113") (name "Net-(X4G-F)") (class "Default")
      (node (ref "R45") (pin "2") (pinfunction "2_2") (pintype "passive"))
      (node (ref "X4") (pin "7") (pinfunction "F_7") (pintype "passive"))
    )
    (net (code "114") (name "Net-(X5A-F)") (class "Default")
      (node (ref "R46") (pin "1") (pinfunction "1_1") (pintype "passive"))
      (node (ref "X5") (pin "1") (pinfunction "F_1") (pintype "passive"))
    )
    (net (code "115") (name "Net-(X5B-F)") (class "Default")
      (node (ref "R39") (pin "1") (pinfunction "1_1") (pintype "passive"))
      (node (ref "X5") (pin "2") (pinfunction "F_2") (pintype "passive"))
    )
    (net (code "116") (name "Net-(X5C-F)") (class "Default")
      (node (ref "R38") (pin "1") (pinfunction "1_1") (pintype "passive"))
      (node (ref "X5") (pin "3") (pinfunction "F_3") (pintype "passive"))
    )
    (net (code "117") (name "Net-(X5D-F)") (class "Default")
      (node (ref "R37") (pin "1") (pinfunction "1_1") (pintype "passive"))
      (node (ref "X5") (pin "4") (pinfunction "F_4") (pintype "passive"))
    )
    (net (code "118") (name "Net-(X5F-F)") (class "Default")
      (node (ref "R36") (pin "1") (pinfunction "1_1") (pintype "passive"))
      (node (ref "X5") (pin "6") (pinfunction "F_6") (pintype "passive"))
    )
    (net (code "119") (name "Net-(X5G-F)") (class "Default")
      (node (ref "R35") (pin "1") (pinfunction "1_1") (pintype "passive"))
      (node (ref "X5") (pin "7") (pinfunction "F_7") (pintype "passive"))
    )
    (net (code "120") (name "unconnected-(IC1-NC.1-Pad2)") (class "Default")
      (node (ref "IC1") (pin "2") (pinfunction "NC.1_2") (pintype "bidirectional"))
    )
    (net (code "121") (name "unconnected-(IC1-NC.2-Pad9)") (class "Default")
      (node (ref "IC1") (pin "9") (pinfunction "NC.2_9") (pintype "bidirectional"))
    )
    (net (code "122") (name "unconnected-(IC1-NC.3-Pad12)") (class "Default")
      (node (ref "IC1") (pin "12") (pinfunction "NC.3_12") (pintype "bidirectional"))
    )
    (net (code "123") (name "unconnected-(IC1-NC.4-Pad14)") (class "Default")
      (node (ref "IC1") (pin "14") (pinfunction "NC.4_14") (pintype "bidirectional"))
    )
    (net (code "124") (name "unconnected-(IC1-NC.5-Pad15)") (class "Default")
      (node (ref "IC1") (pin "15") (pinfunction "NC.5_15") (pintype "bidirectional"))
    )
    (net (code "125") (name "unconnected-(IC1-NC.6-Pad16)") (class "Default")
      (node (ref "IC1") (pin "16") (pinfunction "NC.6_16") (pintype "bidirectional"))
    )
    (net (code "126") (name "unconnected-(IC1-{slash}CEO-Pad13)") (class "Default")
      (node (ref "IC1") (pin "13") (pinfunction "/CEO_13") (pintype "bidirectional"))
    )
    (net (code "127") (name "unconnected-(REG1.2-VOUT2-Pad2)") (class "Default")
      (node (ref "REG1.2") (pin "2") (pinfunction "VOUT2_2") (pintype "bidirectional"))
    )
    (net (code "128") (name "unconnected-(U$2-PadOUT)") (class "Default")
      (node (ref "U$2") (pin "OUT") (pinfunction "OUT_OUT") (pintype "output"))
    )
    (net (code "129") (name "unconnected-(U$2-TRI-PadENA)") (class "Default")
      (node (ref "U$2") (pin "ENA") (pinfunction "TRI_ENA") (pintype "input"))
    )
    (net (code "130") (name "unconnected-(U$3-AREF-Pad42)") (class "Default")
      (node (ref "U$3") (pin "42") (pinfunction "AREF_42") (pintype "bidirectional"))
    )
    (net (code "131") (name "unconnected-(U$3-AVCC-Pad24)") (class "Default")
      (node (ref "U$3") (pin "24") (pinfunction "AVCC_24") (pintype "bidirectional"))
    )
    (net (code "132") (name "unconnected-(U$3-AVCC1-Pad44)") (class "Default")
      (node (ref "U$3") (pin "44") (pinfunction "AVCC1_44") (pintype "bidirectional"))
    )
    (net (code "133") (name "unconnected-(U$3-D+-Pad4)") (class "Default")
      (node (ref "U$3") (pin "4") (pinfunction "D+_4") (pintype "bidirectional"))
    )
    (net (code "134") (name "unconnected-(U$3-D--Pad3)") (class "Default")
      (node (ref "U$3") (pin "3") (pinfunction "D-_3") (pintype "bidirectional"))
    )
    (net (code "135") (name "unconnected-(U$3-GND-Pad15)") (class "Default")
      (node (ref "U$3") (pin "15") (pinfunction "GND_15") (pintype "bidirectional"))
    )
    (net (code "136") (name "unconnected-(U$3-GND1-Pad23)") (class "Default")
      (node (ref "U$3") (pin "23") (pinfunction "GND1_23") (pintype "bidirectional"))
    )
    (net (code "137") (name "unconnected-(U$3-GND2-Pad35)") (class "Default")
      (node (ref "U$3") (pin "35") (pinfunction "GND2_35") (pintype "bidirectional"))
    )
    (net (code "138") (name "unconnected-(U$3-GND3-Pad43)") (class "Default")
      (node (ref "U$3") (pin "43") (pinfunction "GND3_43") (pintype "bidirectional"))
    )
    (net (code "139") (name "unconnected-(U$3-PB4(ADC11)-Pad28)") (class "Default")
      (node (ref "U$3") (pin "28") (pinfunction "PB4(ADC11)_28") (pintype "bidirectional"))
    )
    (net (code "140") (name "unconnected-(U$3-PB5(OC1A{slash}ADC12{slash}~{OC4B})-Pad29)") (class "Default")
      (node (ref "U$3") (pin "29") (pinfunction "PB5(OC1A/ADC12/~{OC4B})_29") (pintype "bidirectional"))
    )
    (net (code "141") (name "unconnected-(U$3-PB6(OC1B{slash}OC4B{slash}ADC13)-Pad30)") (class "Default")
      (node (ref "U$3") (pin "30") (pinfunction "PB6(OC1B/OC4B/ADC13)_30") (pintype "bidirectional"))
    )
    (net (code "142") (name "unconnected-(U$3-PB7(OC0A{slash}OC1C{slash}RTS)-Pad12)") (class "Default")
      (node (ref "U$3") (pin "12") (pinfunction "PB7(OC0A/OC1C/RTS)_12") (pintype "bidirectional"))
    )
    (net (code "143") (name "unconnected-(U$3-PC6(OC3A{slash}~{OC4A})-Pad31)") (class "Default")
      (node (ref "U$3") (pin "31") (pinfunction "PC6(OC3A/~{OC4A})_31") (pintype "bidirectional"))
    )
    (net (code "144") (name "unconnected-(U$3-PC7(ICP3{slash}CLK0{slash}OC4A)-Pad32)") (class "Default")
      (node (ref "U$3") (pin "32") (pinfunction "PC7(ICP3/CLK0/OC4A)_32") (pintype "bidirectional"))
    )
    (net (code "145") (name "unconnected-(U$3-PD0(INT0{slash}OC0B{slash}SCL)-Pad18)") (class "Default")
      (node (ref "U$3") (pin "18") (pinfunction "PD0(INT0/OC0B/SCL)_18") (pintype "bidirectional"))
    )
    (net (code "146") (name "unconnected-(U$3-PD1(INT1{slash}SDA)-Pad19)") (class "Default")
      (node (ref "U$3") (pin "19") (pinfunction "PD1(INT1/SDA)_19") (pintype "bidirectional"))
    )
    (net (code "147") (name "unconnected-(U$3-PD2(INT2{slash}RXD1)-Pad20)") (class "Default")
      (node (ref "U$3") (pin "20") (pinfunction "PD2(INT2/RXD1)_20") (pintype "bidirectional"))
    )
    (net (code "148") (name "unconnected-(U$3-PD3(INT3{slash}TXD1)-Pad21)") (class "Default")
      (node (ref "U$3") (pin "21") (pinfunction "PD3(INT3/TXD1)_21") (pintype "bidirectional"))
    )
    (net (code "149") (name "unconnected-(U$3-PD4(ICP1{slash}ADC8)-Pad25)") (class "Default")
      (node (ref "U$3") (pin "25") (pinfunction "PD4(ICP1/ADC8)_25") (pintype "bidirectional"))
    )
    (net (code "150") (name "unconnected-(U$3-PD5(XCK{slash}CTS)-Pad22)") (class "Default")
      (node (ref "U$3") (pin "22") (pinfunction "PD5(XCK/CTS)_22") (pintype "bidirectional"))
    )
    (net (code "151") (name "unconnected-(U$3-PD6(T1{slash}ADC9{slash}~{OC4D})-Pad26)") (class "Default")
      (node (ref "U$3") (pin "26") (pinfunction "PD6(T1/ADC9/~{OC4D})_26") (pintype "bidirectional"))
    )
    (net (code "152") (name "unconnected-(U$3-PD7(OC4D{slash}ADC10{slash}T0)-Pad27)") (class "Default")
      (node (ref "U$3") (pin "27") (pinfunction "PD7(OC4D/ADC10/T0)_27") (pintype "bidirectional"))
    )
    (net (code "153") (name "unconnected-(U$3-PE2(~{HWB})-Pad33)") (class "Default")
      (node (ref "U$3") (pin "33") (pinfunction "PE2(~{HWB})_33") (pintype "bidirectional"))
    )
    (net (code "154") (name "unconnected-(U$3-PE6(INT.6{slash}AIN0)-Pad1)") (class "Default")
      (node (ref "U$3") (pin "1") (pinfunction "PE6(INT.6/AIN0)_1") (pintype "bidirectional"))
    )
    (net (code "155") (name "unconnected-(U$3-PF0(ADC0)-Pad41)") (class "Default")
      (node (ref "U$3") (pin "41") (pinfunction "PF0(ADC0)_41") (pintype "bidirectional"))
    )
    (net (code "156") (name "unconnected-(U$3-PF1(ADC1)-Pad40)") (class "Default")
      (node (ref "U$3") (pin "40") (pinfunction "PF1(ADC1)_40") (pintype "bidirectional"))
    )
    (net (code "157") (name "unconnected-(U$3-UCAP-Pad6)") (class "Default")
      (node (ref "U$3") (pin "6") (pinfunction "UCAP_6") (pintype "bidirectional"))
    )
    (net (code "158") (name "unconnected-(U$3-UGND-Pad5)") (class "Default")
      (node (ref "U$3") (pin "5") (pinfunction "UGND_5") (pintype "bidirectional"))
    )
    (net (code "159") (name "unconnected-(U$3-UVCC-Pad2)") (class "Default")
      (node (ref "U$3") (pin "2") (pinfunction "UVCC_2") (pintype "bidirectional"))
    )
    (net (code "160") (name "unconnected-(U$3-VBUS-Pad7)") (class "Default")
      (node (ref "U$3") (pin "7") (pinfunction "VBUS_7") (pintype "bidirectional"))
    )
    (net (code "161") (name "unconnected-(U$3-VCC-Pad14)") (class "Default")
      (node (ref "U$3") (pin "14") (pinfunction "VCC_14") (pintype "bidirectional"))
    )
    (net (code "162") (name "unconnected-(U$3-VCC1-Pad34)") (class "Default")
      (node (ref "U$3") (pin "34") (pinfunction "VCC1_34") (pintype "bidirectional"))
    )
    (net (code "163") (name "unconnected-(U$3-XTAL1-Pad17)") (class "Default")
      (node (ref "U$3") (pin "17") (pinfunction "XTAL1_17") (pintype "bidirectional"))
    )
    (net (code "164") (name "unconnected-(U$3-XTAL2-Pad16)") (class "Default")
      (node (ref "U$3") (pin "16") (pinfunction "XTAL2_16") (pintype "bidirectional"))
    )
    (net (code "165") (name "unconnected-(U$3-{slash}RESET-Pad13)") (class "Default")
      (node (ref "U$3") (pin "13") (pinfunction "/RESET_13") (pintype "bidirectional"))
    )
    (net (code "166") (name "unconnected-(U1A-IO_L27P_0-PadP135)") (class "Default")
      (node (ref "U1") (pin "P135") (pinfunction "IO_L27P_0_P135") (pintype "bidirectional"))
    )
    (net (code "167") (name "unconnected-(U1A-IO_L30N_0-PadP132)") (class "Default")
      (node (ref "U1") (pin "P132") (pinfunction "IO_L30N_0_P132") (pintype "bidirectional"))
    )
    (net (code "168") (name "unconnected-(U1A-IO_L30P_0-PadP131)") (class "Default")
      (node (ref "U1") (pin "P131") (pinfunction "IO_L30P_0_P131") (pintype "bidirectional"))
    )
    (net (code "169") (name "unconnected-(U1A-IO_L31N_0-PadP130)") (class "Default")
      (node (ref "U1") (pin "P130") (pinfunction "IO_L31N_0_P130") (pintype "bidirectional"))
    )
    (net (code "170") (name "unconnected-(U1A-IO_L31P_0VREF_0-PadP129)") (class "Default")
      (node (ref "U1") (pin "P129") (pinfunction "IO_L31P_0VREF_0_P129") (pintype "bidirectional"))
    )
    (net (code "171") (name "unconnected-(U1A-IO_L32N_0GCLK7-PadP128)") (class "Default")
      (node (ref "U1") (pin "P128") (pinfunction "IO_L32N_0GCLK7_P128") (pintype "bidirectional"))
    )
    (net (code "172") (name "unconnected-(U1A-IO_L32P_0GCLK6-PadP127)") (class "Default")
      (node (ref "U1") (pin "P127") (pinfunction "IO_L32P_0GCLK6_P127") (pintype "bidirectional"))
    )
    (net (code "173") (name "unconnected-(U1C-IO-PadP116)") (class "Default")
      (node (ref "U1") (pin "P116") (pinfunction "IO_P116") (pintype "bidirectional"))
    )
    (net (code "174") (name "unconnected-(U1C-IO_L01N_1VRP_1-PadP113)") (class "Default")
      (node (ref "U1") (pin "P113") (pinfunction "IO_L01N_1VRP_1_P113") (pintype "bidirectional"))
    )
    (net (code "175") (name "unconnected-(U1C-IO_L01P_1VRN_1-PadP112)") (class "Default")
      (node (ref "U1") (pin "P112") (pinfunction "IO_L01P_1VRN_1_P112") (pintype "bidirectional"))
    )
    (net (code "176") (name "unconnected-(U1C-IO_L28N_1-PadP119)") (class "Default")
      (node (ref "U1") (pin "P119") (pinfunction "IO_L28N_1_P119") (pintype "bidirectional"))
    )
    (net (code "177") (name "unconnected-(U1C-IO_L28P_1-PadP118)") (class "Default")
      (node (ref "U1") (pin "P118") (pinfunction "IO_L28P_1_P118") (pintype "bidirectional"))
    )
    (net (code "178") (name "unconnected-(U1C-IO_L31N_1VREF_1-PadP123)") (class "Default")
      (node (ref "U1") (pin "P123") (pinfunction "IO_L31N_1VREF_1_P123") (pintype "bidirectional"))
    )
    (net (code "179") (name "unconnected-(U1C-IO_L31P_1-PadP122)") (class "Default")
      (node (ref "U1") (pin "P122") (pinfunction "IO_L31P_1_P122") (pintype "bidirectional"))
    )
    (net (code "180") (name "unconnected-(U1C-IO_L32N_1GCLK5-PadP125)") (class "Default")
      (node (ref "U1") (pin "P125") (pinfunction "IO_L32N_1GCLK5_P125") (pintype "bidirectional"))
    )
    (net (code "181") (name "unconnected-(U1C-IO_L32P_1GCLK4-PadP124)") (class "Default")
      (node (ref "U1") (pin "P124") (pinfunction "IO_L32P_1GCLK4_P124") (pintype "bidirectional"))
    )
    (net (code "182") (name "unconnected-(U1I-IO_L32N_5GCLK3-PadP53)") (class "Default")
      (node (ref "U1") (pin "P53") (pinfunction "IO_L32N_5GCLK3_P53") (pintype "bidirectional"))
    )
    (net (code "183") (name "unconnected-(U1I-IO_L32P_5GCLK2-PadP52)") (class "Default")
      (node (ref "U1") (pin "P52") (pinfunction "IO_L32P_5GCLK2_P52") (pintype "bidirectional"))
    )
    (net (code "184") (name "unconnected-(U1J-IO_L01N_6VRP_6-PadP36)") (class "Default")
      (node (ref "U1") (pin "P36") (pinfunction "IO_L01N_6VRP_6_P36") (pintype "bidirectional"))
    )
    (net (code "185") (name "unconnected-(U1J-IO_L01P_6VRN_6-PadP35)") (class "Default")
      (node (ref "U1") (pin "P35") (pinfunction "IO_L01P_6VRN_6_P35") (pintype "bidirectional"))
    )
    (net (code "186") (name "unconnected-(U1J-IO_L20N_6-PadP33)") (class "Default")
      (node (ref "U1") (pin "P33") (pinfunction "IO_L20N_6_P33") (pintype "bidirectional"))
    )
    (net (code "187") (name "unconnected-(U1J-IO_L20P_6-PadP32)") (class "Default")
      (node (ref "U1") (pin "P32") (pinfunction "IO_L20P_6_P32") (pintype "bidirectional"))
    )
    (net (code "188") (name "unconnected-(U1J-IO_L21N_6-PadP31)") (class "Default")
      (node (ref "U1") (pin "P31") (pinfunction "IO_L21N_6_P31") (pintype "bidirectional"))
    )
    (net (code "189") (name "unconnected-(U1J-IO_L21P_6-PadP30)") (class "Default")
      (node (ref "U1") (pin "P30") (pinfunction "IO_L21P_6_P30") (pintype "bidirectional"))
    )
    (net (code "190") (name "unconnected-(U1J-IO_L22N_6-PadP28)") (class "Default")
      (node (ref "U1") (pin "P28") (pinfunction "IO_L22N_6_P28") (pintype "bidirectional"))
    )
    (net (code "191") (name "unconnected-(U1J-IO_L22P_6-PadP27)") (class "Default")
      (node (ref "U1") (pin "P27") (pinfunction "IO_L22P_6_P27") (pintype "bidirectional"))
    )
    (net (code "192") (name "unconnected-(U1J-IO_L23N_6-PadP26)") (class "Default")
      (node (ref "U1") (pin "P26") (pinfunction "IO_L23N_6_P26") (pintype "bidirectional"))
    )
    (net (code "193") (name "unconnected-(U1J-IO_L23P_6-PadP25)") (class "Default")
      (node (ref "U1") (pin "P25") (pinfunction "IO_L23P_6_P25") (pintype "bidirectional"))
    )
    (net (code "194") (name "unconnected-(U1J-IO_L24N_6VREF_6-PadP24)") (class "Default")
      (node (ref "U1") (pin "P24") (pinfunction "IO_L24N_6VREF_6_P24") (pintype "bidirectional"))
    )
    (net (code "195") (name "unconnected-(U1J-IO_L24P_6-PadP23)") (class "Default")
      (node (ref "U1") (pin "P23") (pinfunction "IO_L24P_6_P23") (pintype "bidirectional"))
    )
    (net (code "196") (name "unconnected-(U1J-IO_L40N_6-PadP21)") (class "Default")
      (node (ref "U1") (pin "P21") (pinfunction "IO_L40N_6_P21") (pintype "bidirectional"))
    )
    (net (code "197") (name "unconnected-(U1J-IO_L40P_6VREF_6-PadP20)") (class "Default")
      (node (ref "U1") (pin "P20") (pinfunction "IO_L40P_6VREF_6_P20") (pintype "bidirectional"))
    )
    (net (code "198") (name "unconnected-(U1L-IOVREF_7-PadP4)") (class "Default")
      (node (ref "U1") (pin "P4") (pinfunction "IOVREF_7_P4") (pintype "bidirectional"))
    )
    (net (code "199") (name "unconnected-(U1L-IO_L01N_7VRP_7-PadP2)") (class "Default")
      (node (ref "U1") (pin "P2") (pinfunction "IO_L01N_7VRP_7_P2") (pintype "bidirectional"))
    )
    (net (code "200") (name "unconnected-(U1L-IO_L01P_7VRN_7-PadP1)") (class "Default")
      (node (ref "U1") (pin "P1") (pinfunction "IO_L01P_7VRN_7_P1") (pintype "bidirectional"))
    )
    (net (code "201") (name "unconnected-(U1L-IO_L20N_7-PadP6)") (class "Default")
      (node (ref "U1") (pin "P6") (pinfunction "IO_L20N_7_P6") (pintype "bidirectional"))
    )
    (net (code "202") (name "unconnected-(U1L-IO_L20P_7-PadP5)") (class "Default")
      (node (ref "U1") (pin "P5") (pinfunction "IO_L20P_7_P5") (pintype "bidirectional"))
    )
    (net (code "203") (name "unconnected-(U1L-IO_L21N_7-PadP8)") (class "Default")
      (node (ref "U1") (pin "P8") (pinfunction "IO_L21N_7_P8") (pintype "bidirectional"))
    )
    (net (code "204") (name "unconnected-(U1L-IO_L21P_7-PadP7)") (class "Default")
      (node (ref "U1") (pin "P7") (pinfunction "IO_L21P_7_P7") (pintype "bidirectional"))
    )
    (net (code "205") (name "unconnected-(U1L-IO_L22N_7-PadP11)") (class "Default")
      (node (ref "U1") (pin "P11") (pinfunction "IO_L22N_7_P11") (pintype "bidirectional"))
    )
    (net (code "206") (name "unconnected-(U1L-IO_L22P_7-PadP10)") (class "Default")
      (node (ref "U1") (pin "P10") (pinfunction "IO_L22P_7_P10") (pintype "bidirectional"))
    )
    (net (code "207") (name "unconnected-(U1L-IO_L23N_7-PadP13)") (class "Default")
      (node (ref "U1") (pin "P13") (pinfunction "IO_L23N_7_P13") (pintype "bidirectional"))
    )
    (net (code "208") (name "unconnected-(U1L-IO_L23P_7-PadP12)") (class "Default")
      (node (ref "U1") (pin "P12") (pinfunction "IO_L23P_7_P12") (pintype "bidirectional"))
    )
    (net (code "209") (name "unconnected-(U1L-IO_L24N_7-PadP15)") (class "Default")
      (node (ref "U1") (pin "P15") (pinfunction "IO_L24N_7_P15") (pintype "bidirectional"))
    )
    (net (code "210") (name "unconnected-(U1L-IO_L24P_7-PadP14)") (class "Default")
      (node (ref "U1") (pin "P14") (pinfunction "IO_L24P_7_P14") (pintype "bidirectional"))
    )
    (net (code "211") (name "unconnected-(U1L-IO_L40N_7VREF_7-PadP18)") (class "Default")
      (node (ref "U1") (pin "P18") (pinfunction "IO_L40N_7VREF_7_P18") (pintype "bidirectional"))
    )
    (net (code "212") (name "unconnected-(U1L-IO_L40P_7-PadP17)") (class "Default")
      (node (ref "U1") (pin "P17") (pinfunction "IO_L40P_7_P17") (pintype "bidirectional"))
    )
    (net (code "213") (name "unconnected-(U1N-HSWAP_EN-PadP142)") (class "Default")
      (node (ref "U1") (pin "P142") (pinfunction "HSWAP_EN_P142") (pintype "bidirectional"))
    )
    (net (code "214") (name "unconnected-(X1-3-Pad2)") (class "Default")
      (node (ref "X1") (pin "2") (pinfunction "3_2") (pintype "passive"))
    )
    (net (code "215") (name "unconnected-(X2-Pad10)") (class "Default")
      (node (ref "X2") (pin "10") (pinfunction "10_10") (pintype "passive"))
    )
    (net (code "216") (name "unconnected-(X2-Pad12)") (class "Default")
      (node (ref "X2") (pin "12") (pinfunction "12_12") (pintype "passive"))
    )
    (net (code "217") (name "unconnected-(X3-Pad2)") (class "Default")
      (node (ref "X3") (pin "2") (pinfunction "2_2") (pintype "passive"))
    )
    (net (code "218") (name "unconnected-(X3-Pad8)") (class "Default")
      (node (ref "X3") (pin "8") (pinfunction "8_8") (pintype "passive"))
    )
    (net (code "219") (name "unconnected-(X4-PadG2)") (class "Default")
      (node (ref "X4") (pin "G2") (pinfunction "G2_G2") (pintype "passive"))
    )
    (net (code "220") (name "unconnected-(X5-PadG2)") (class "Default")
      (node (ref "X5") (pin "G2") (pinfunction "G2_G2") (pintype "passive"))
    )
  )
)
